# avalon_module.net
KiCad netlist of a schematic drawn in EAGLE
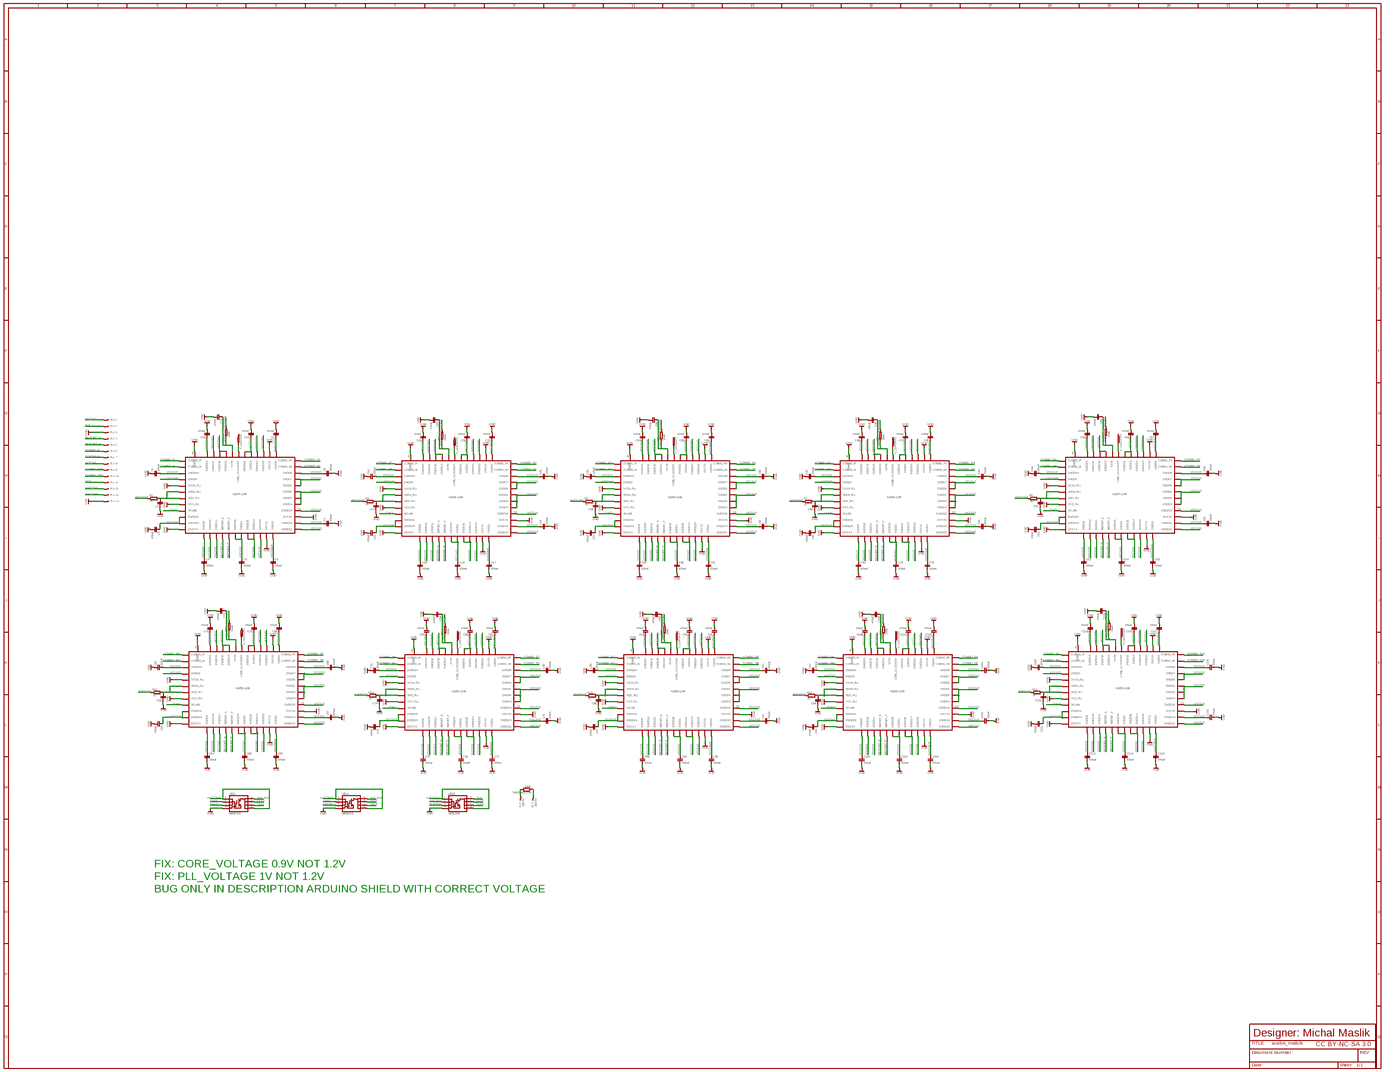
[diagram p0: schematic, sheet 1, overview]
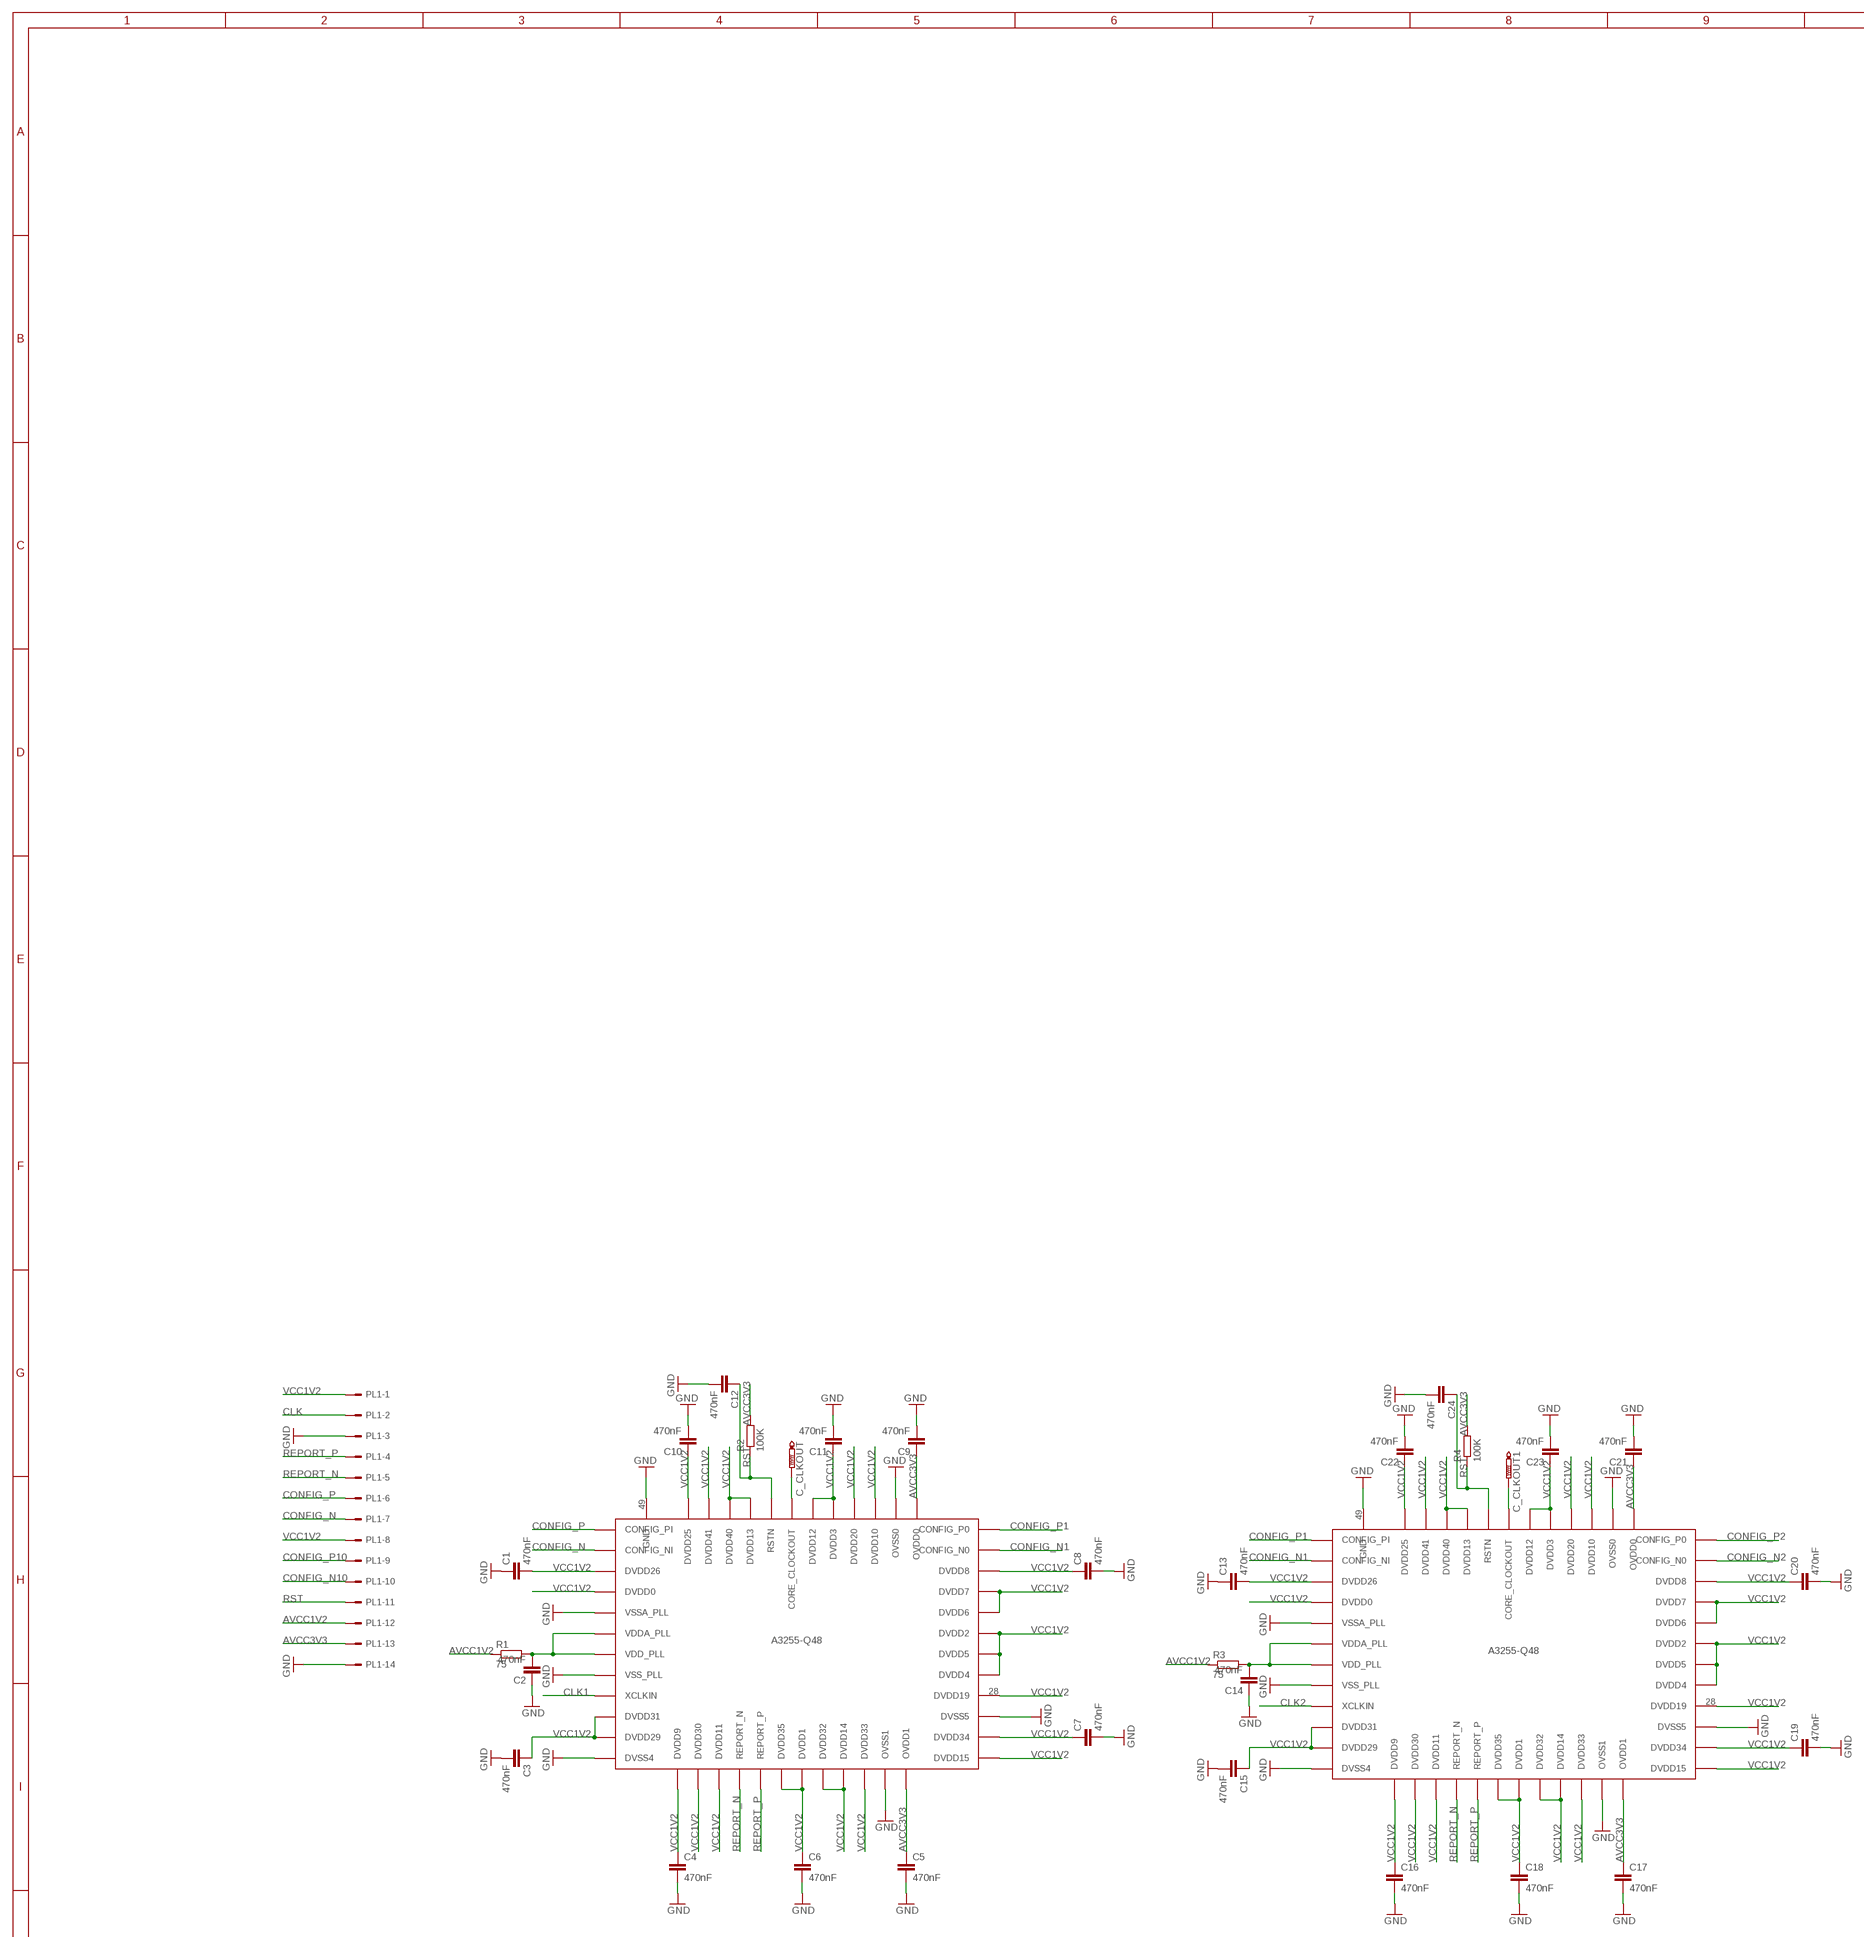
[diagram p1: schematic, sheet 1, part 1 of 6]
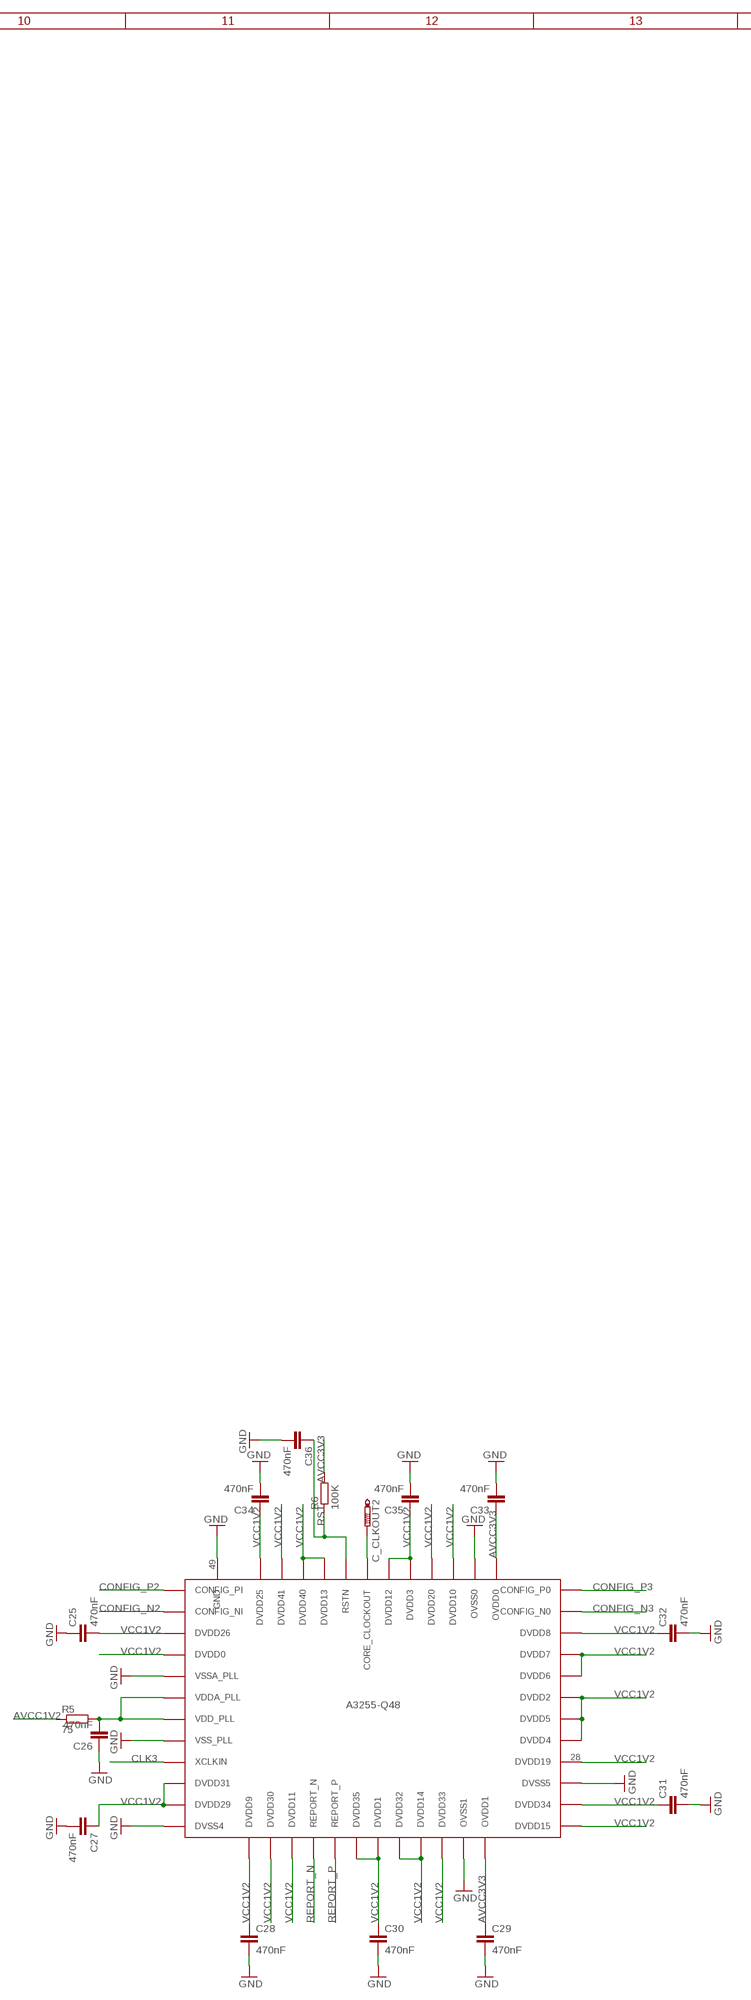
[diagram p2: schematic, sheet 1, part 2 of 6]
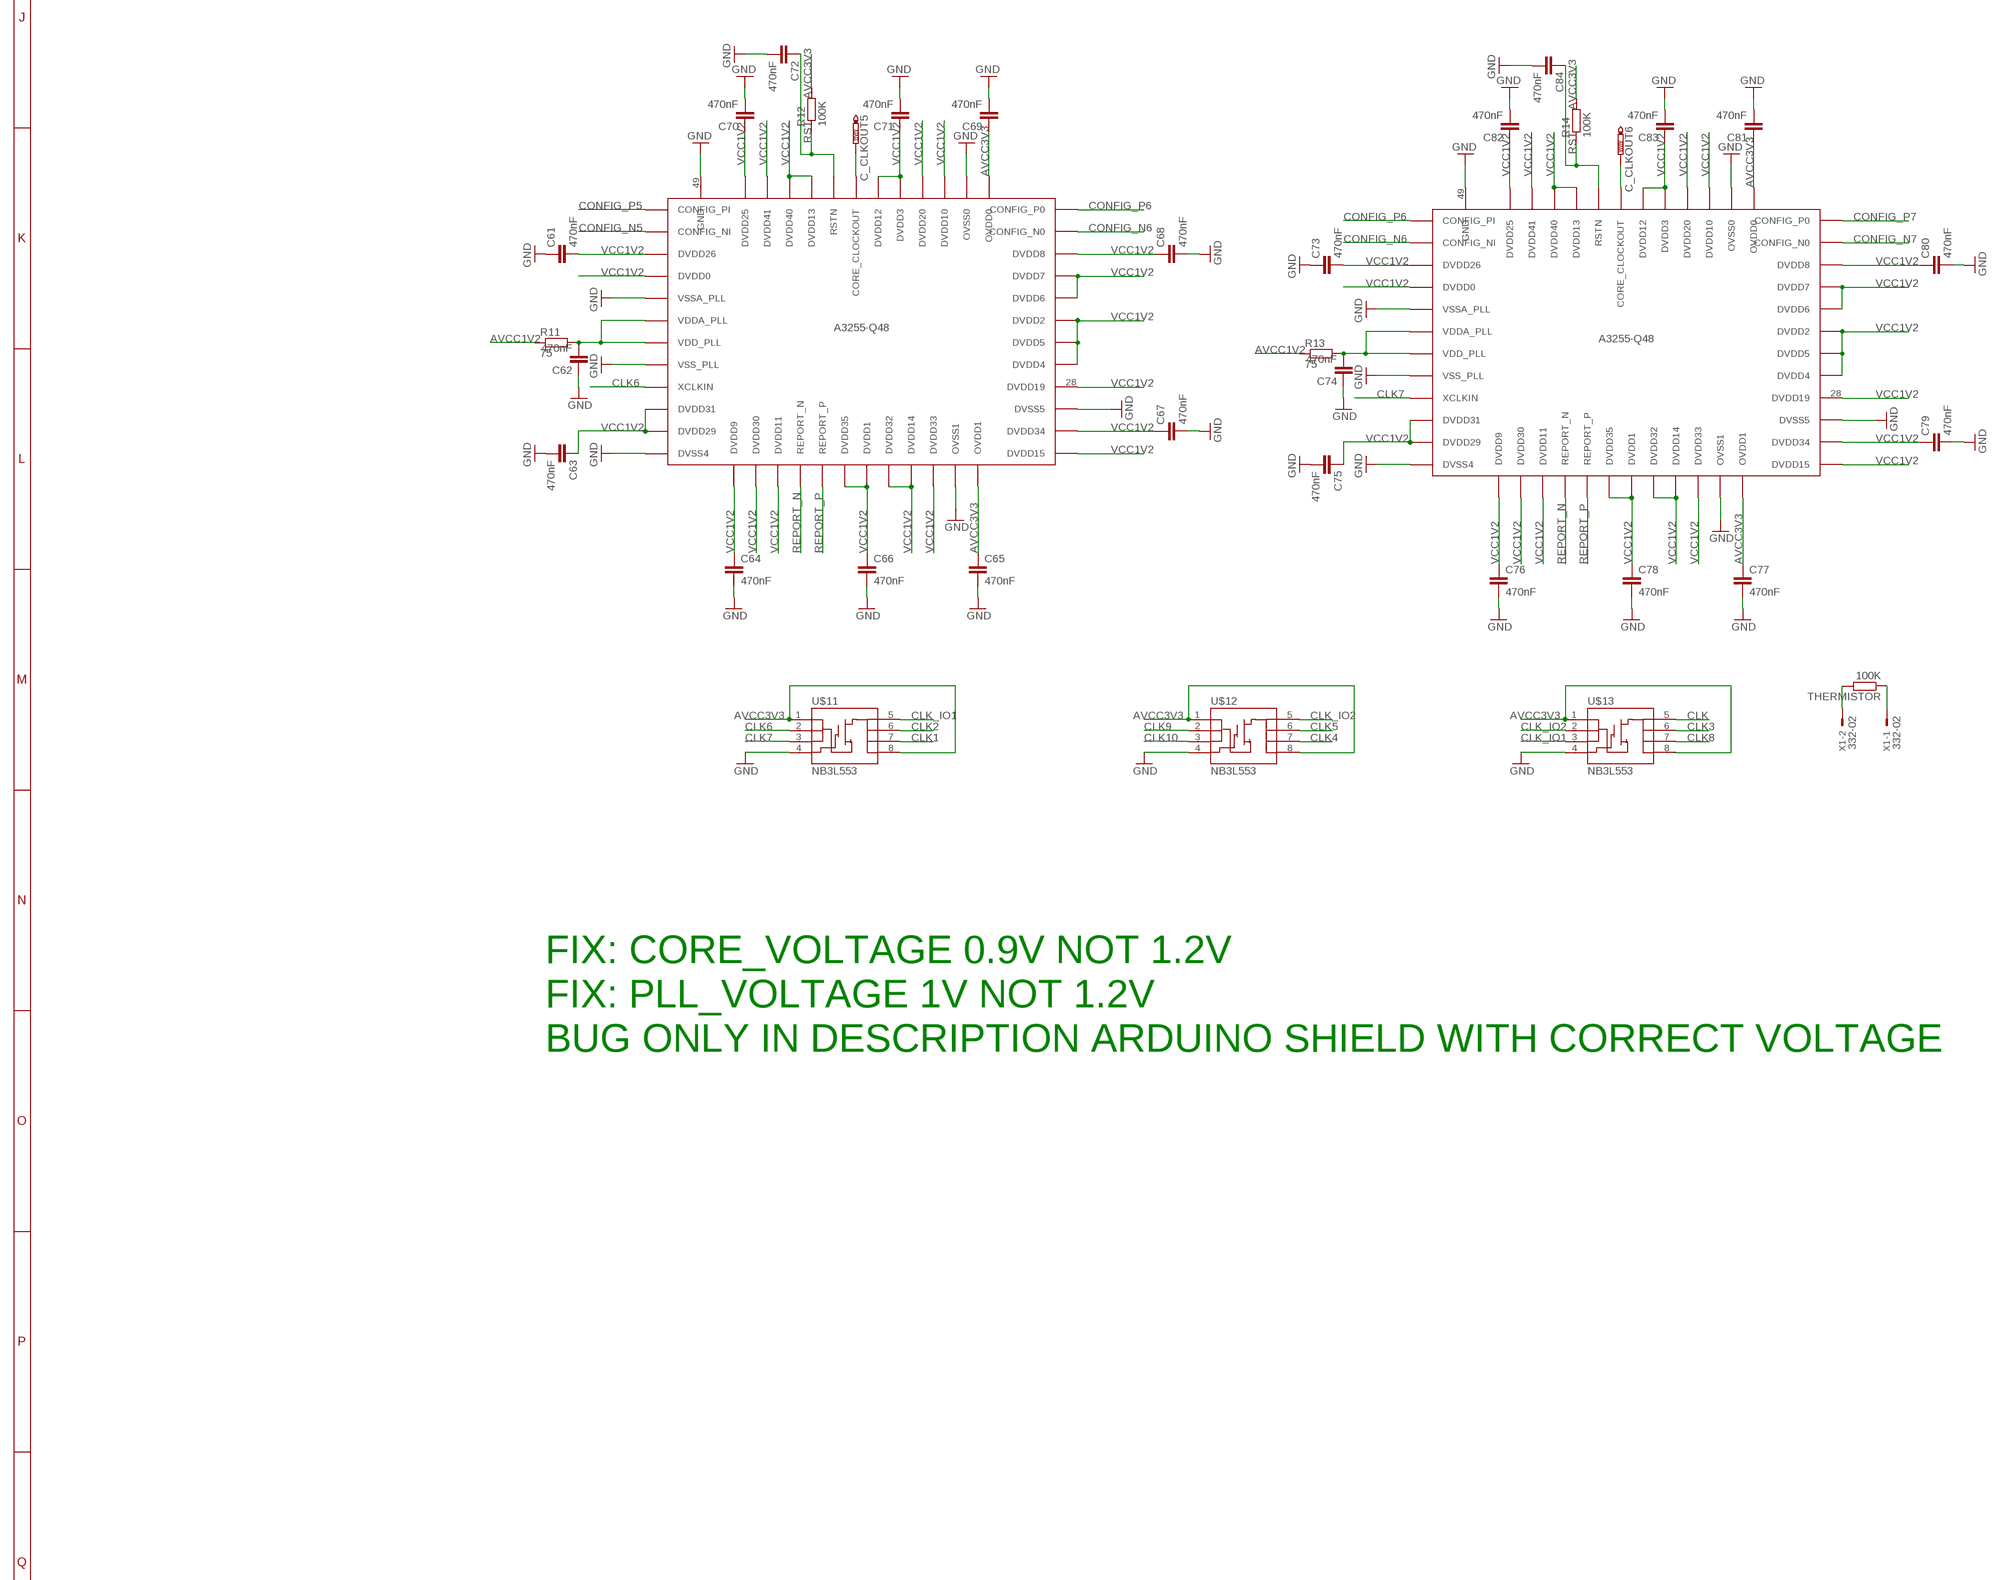
[diagram p3: schematic, sheet 1, part 3 of 6]
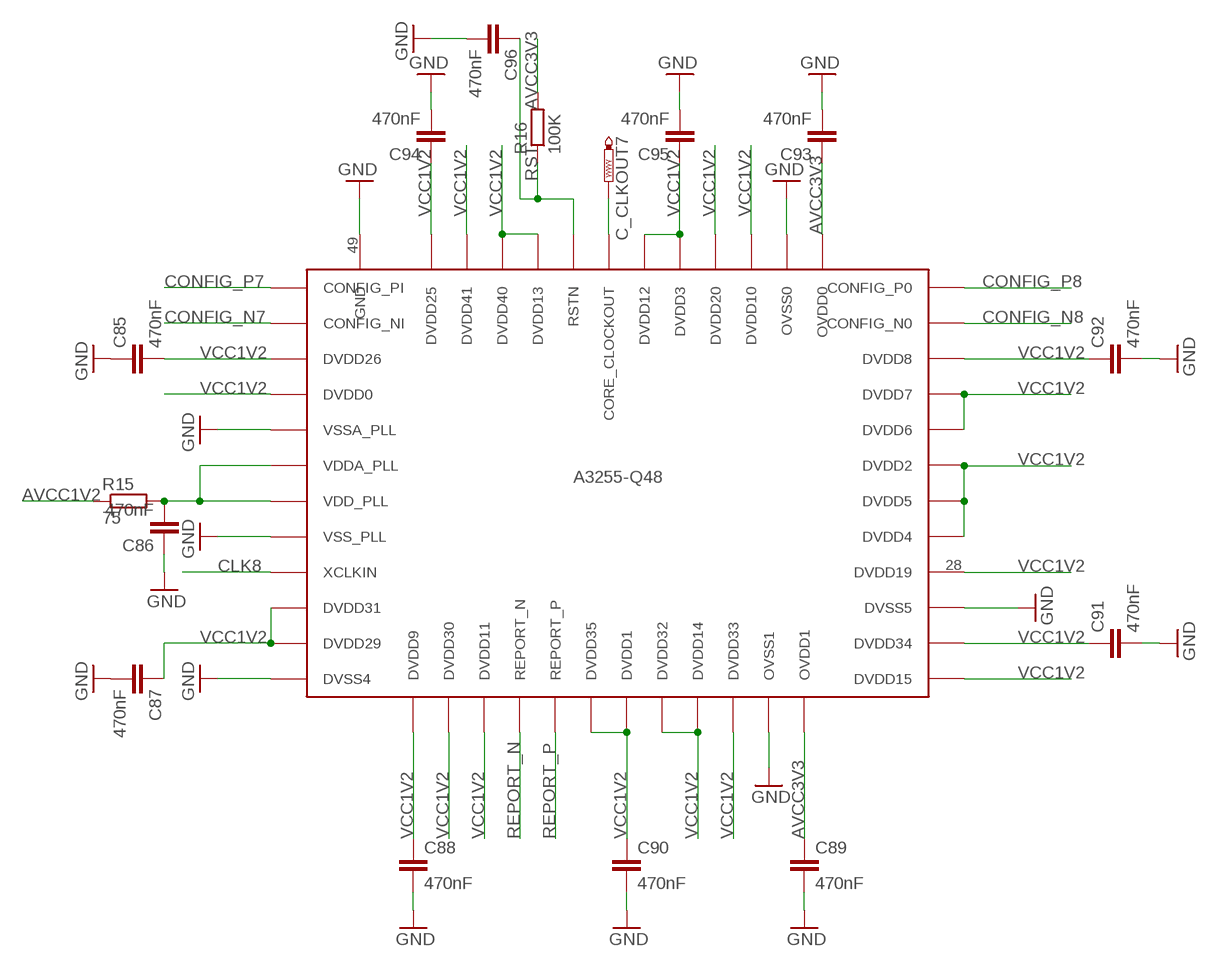
[diagram p4: schematic, sheet 1, part 4 of 6]
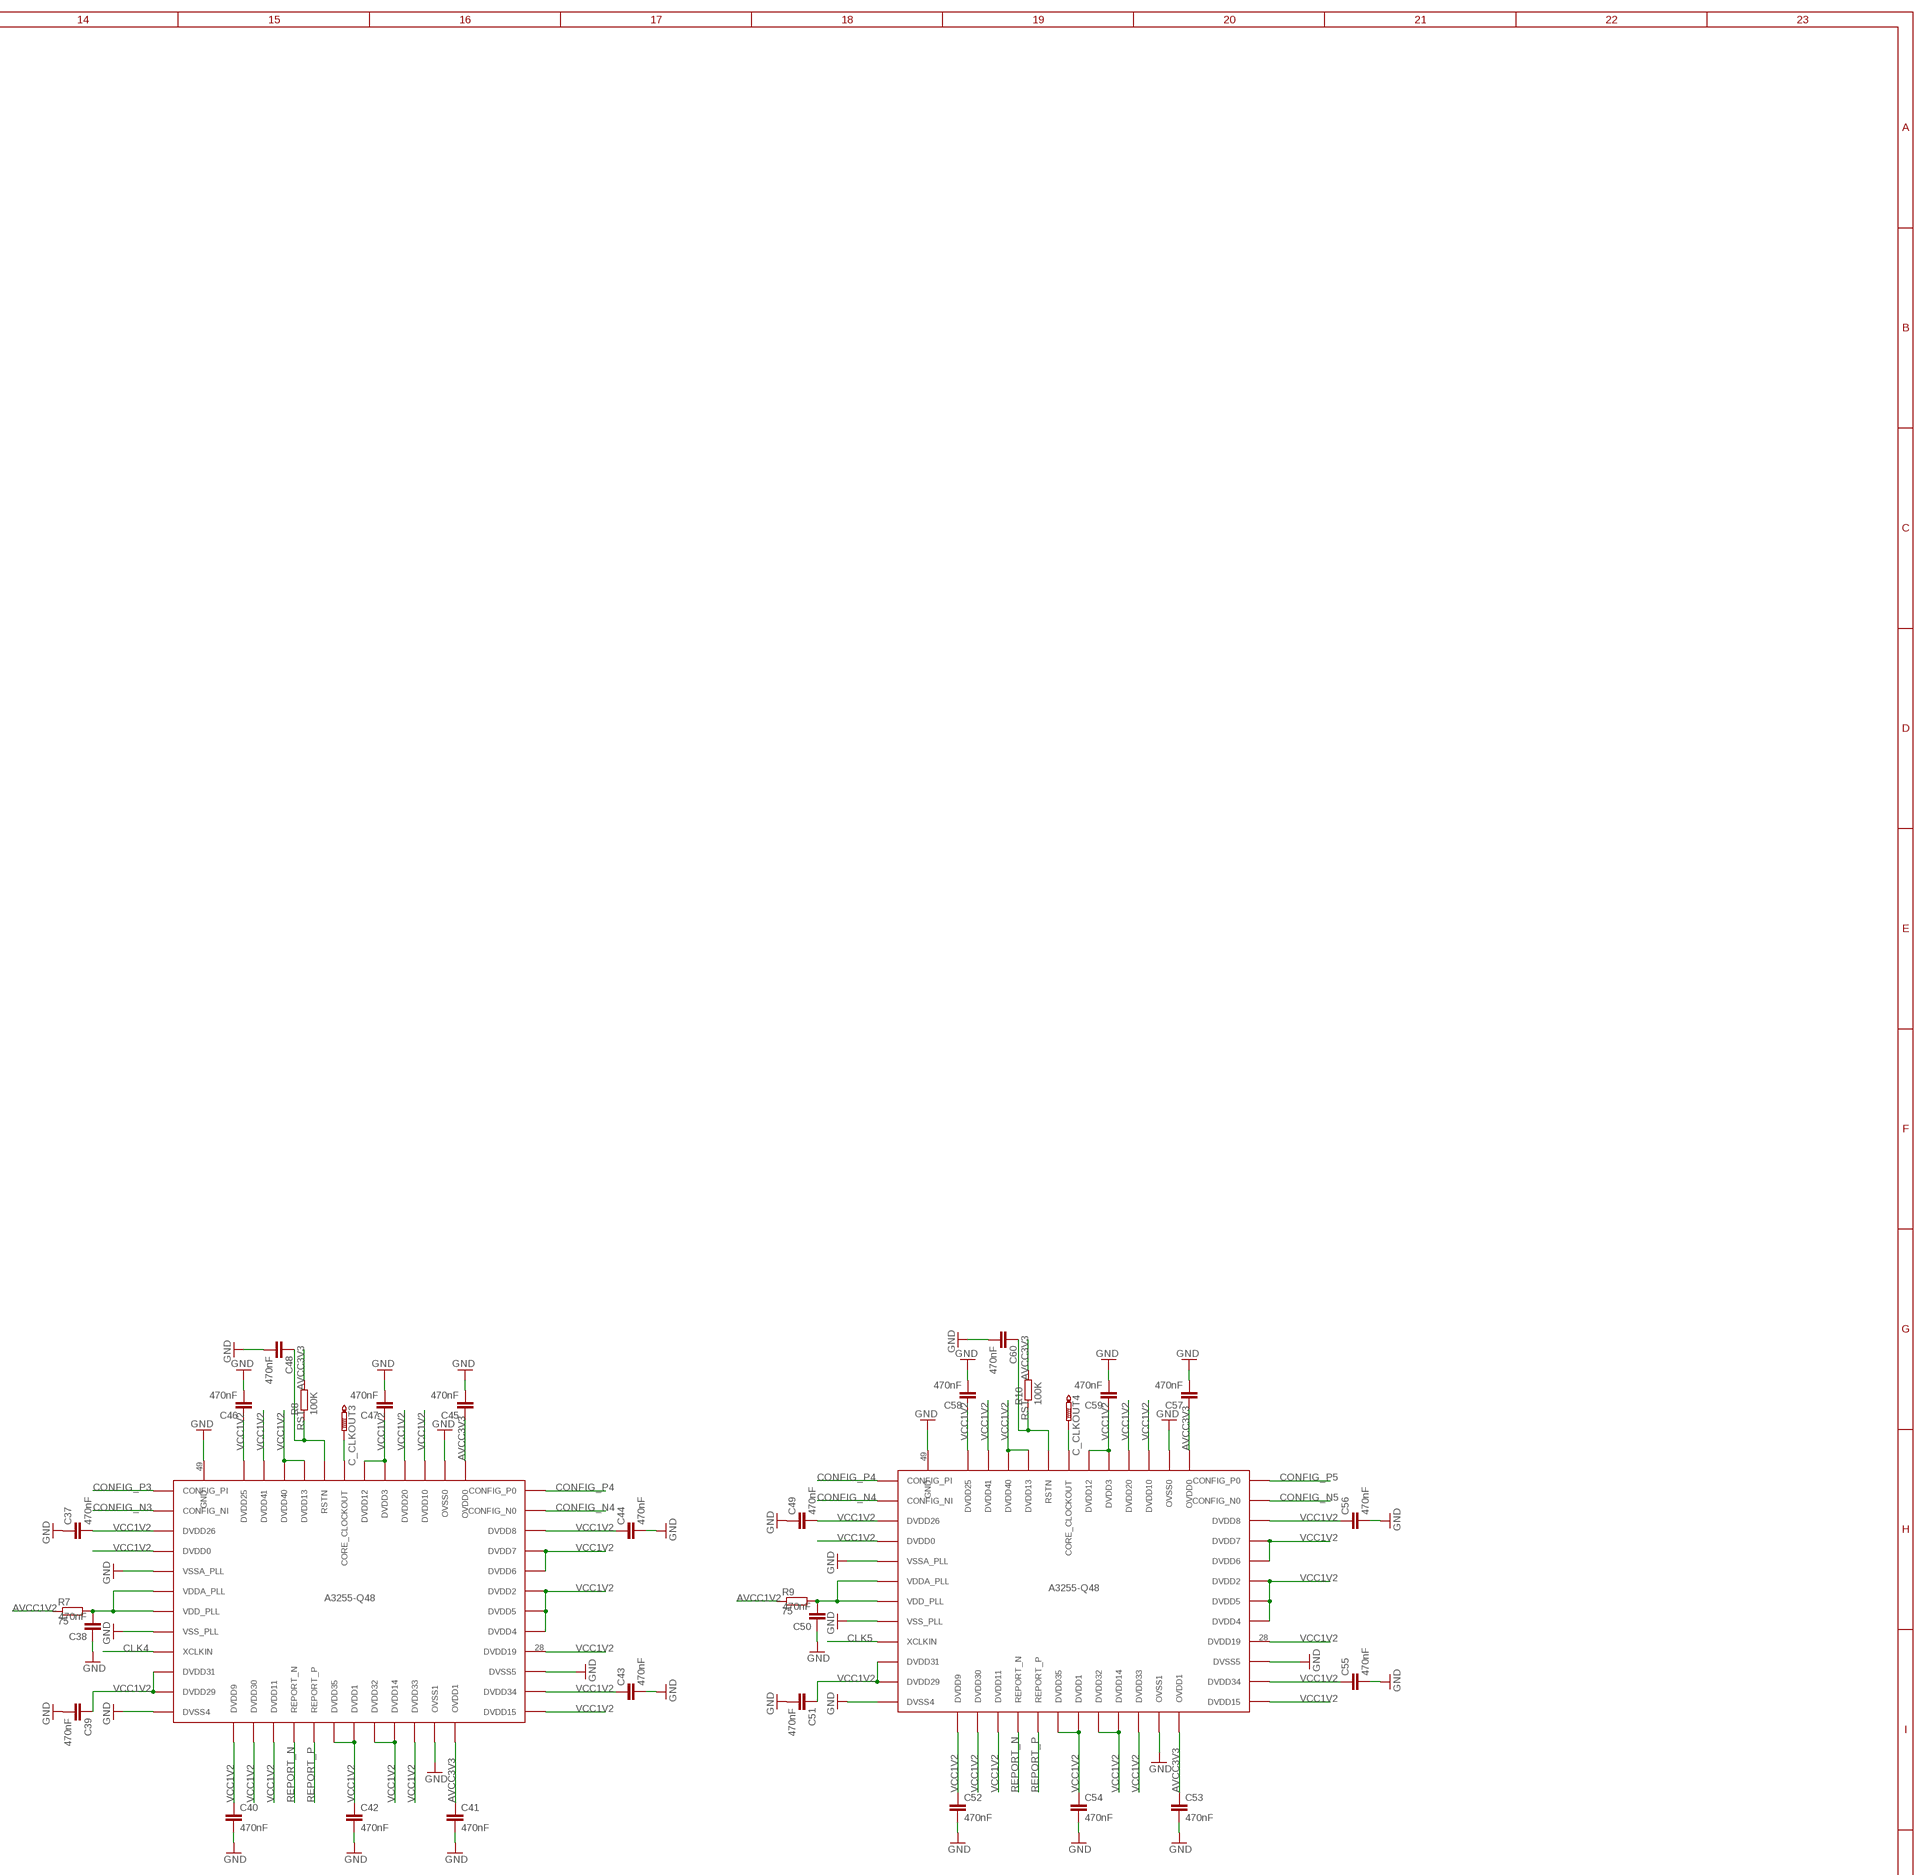
[diagram p5: schematic, sheet 1, part 5 of 6]
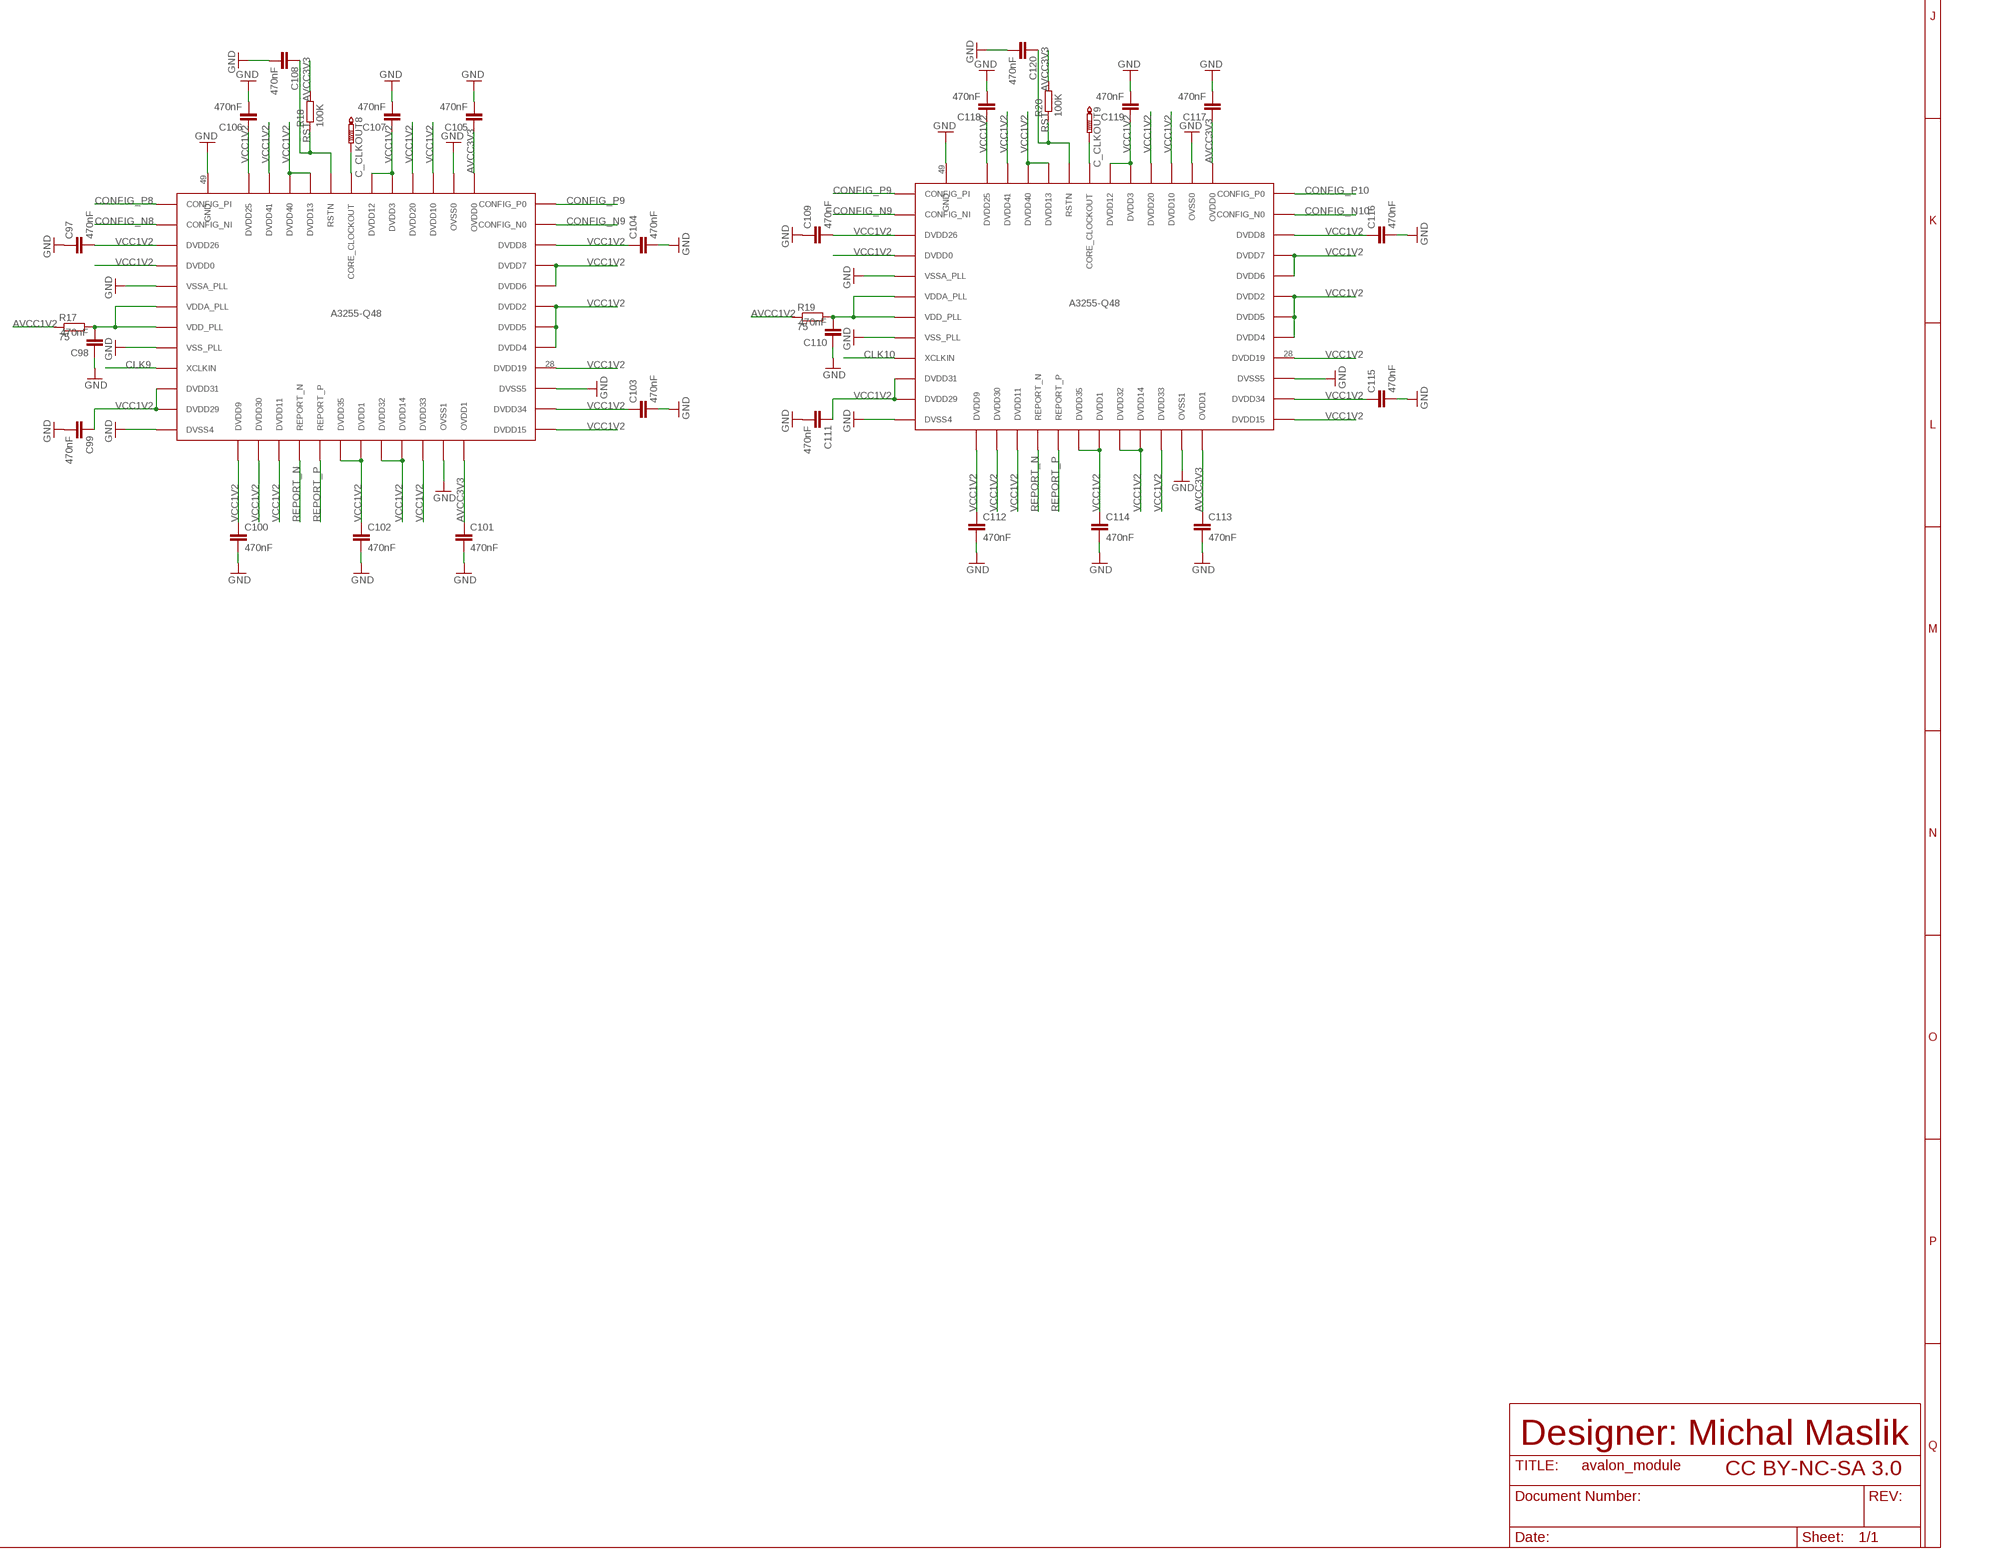
[diagram p6: schematic, sheet 1, part 6 of 6]

(export (version "E")
  (design (tool "Eeschema 10.0.6"))
  (components
    (comp (ref "C1")
      (value "470nF")
      (footprint "eagle-import:C0603K")
      (libsource (lib "eagle-import") (part "C-EUC0603K"))
    )
    (comp (ref "C2")
      (value "470nF")
      (footprint "eagle-import:C0603K")
      (libsource (lib "eagle-import") (part "C-EUC0603K"))
    )
    (comp (ref "C3")
      (value "470nF")
      (footprint "eagle-import:C0603K")
      (libsource (lib "eagle-import") (part "C-EUC0603K"))
    )
    (comp (ref "C4")
      (value "470nF")
      (footprint "eagle-import:C0603K")
      (libsource (lib "eagle-import") (part "C-EUC0603K"))
    )
    (comp (ref "C5")
      (value "470nF")
      (footprint "eagle-import:C0603K")
      (libsource (lib "eagle-import") (part "C-EUC0603K"))
    )
    (comp (ref "C6")
      (value "470nF")
      (footprint "eagle-import:C0603K")
      (libsource (lib "eagle-import") (part "C-EUC0603K"))
    )
    (comp (ref "C7")
      (value "470nF")
      (footprint "eagle-import:C0603K")
      (libsource (lib "eagle-import") (part "C-EUC0603K"))
    )
    (comp (ref "C8")
      (value "470nF")
      (footprint "eagle-import:C0603K")
      (libsource (lib "eagle-import") (part "C-EUC0603K"))
    )
    (comp (ref "C9")
      (value "470nF")
      (footprint "eagle-import:C0603K")
      (libsource (lib "eagle-import") (part "C-EUC0603K"))
    )
    (comp (ref "C10")
      (value "470nF")
      (footprint "eagle-import:C0603K")
      (libsource (lib "eagle-import") (part "C-EUC0603K"))
    )
    (comp (ref "C11")
      (value "470nF")
      (footprint "eagle-import:C0603K")
      (libsource (lib "eagle-import") (part "C-EUC0603K"))
    )
    (comp (ref "C12")
      (value "470nF")
      (footprint "eagle-import:C0603K")
      (libsource (lib "eagle-import") (part "C-EUC0603K"))
    )
    (comp (ref "C13")
      (value "470nF")
      (footprint "eagle-import:C0603K")
      (libsource (lib "eagle-import") (part "C-EUC0603K"))
    )
    (comp (ref "C14")
      (value "470nF")
      (footprint "eagle-import:C0603K")
      (libsource (lib "eagle-import") (part "C-EUC0603K"))
    )
    (comp (ref "C15")
      (value "470nF")
      (footprint "eagle-import:C0603K")
      (libsource (lib "eagle-import") (part "C-EUC0603K"))
    )
    (comp (ref "C16")
      (value "470nF")
      (footprint "eagle-import:C0603K")
      (libsource (lib "eagle-import") (part "C-EUC0603K"))
    )
    (comp (ref "C17")
      (value "470nF")
      (footprint "eagle-import:C0603K")
      (libsource (lib "eagle-import") (part "C-EUC0603K"))
    )
    (comp (ref "C18")
      (value "470nF")
      (footprint "eagle-import:C0603K")
      (libsource (lib "eagle-import") (part "C-EUC0603K"))
    )
    (comp (ref "C19")
      (value "470nF")
      (footprint "eagle-import:C0603K")
      (libsource (lib "eagle-import") (part "C-EUC0603K"))
    )
    (comp (ref "C20")
      (value "470nF")
      (footprint "eagle-import:C0603K")
      (libsource (lib "eagle-import") (part "C-EUC0603K"))
    )
    (comp (ref "C21")
      (value "470nF")
      (footprint "eagle-import:C0603K")
      (libsource (lib "eagle-import") (part "C-EUC0603K"))
    )
    (comp (ref "C22")
      (value "470nF")
      (footprint "eagle-import:C0603K")
      (libsource (lib "eagle-import") (part "C-EUC0603K"))
    )
    (comp (ref "C23")
      (value "470nF")
      (footprint "eagle-import:C0603K")
      (libsource (lib "eagle-import") (part "C-EUC0603K"))
    )
    (comp (ref "C24")
      (value "470nF")
      (footprint "eagle-import:C0603K")
      (libsource (lib "eagle-import") (part "C-EUC0603K"))
    )
    (comp (ref "C25")
      (value "470nF")
      (footprint "eagle-import:C0603K")
      (libsource (lib "eagle-import") (part "C-EUC0603K"))
    )
    (comp (ref "C26")
      (value "470nF")
      (footprint "eagle-import:C0603K")
      (libsource (lib "eagle-import") (part "C-EUC0603K"))
    )
    (comp (ref "C27")
      (value "470nF")
      (footprint "eagle-import:C0603K")
      (libsource (lib "eagle-import") (part "C-EUC0603K"))
    )
    (comp (ref "C28")
      (value "470nF")
      (footprint "eagle-import:C0603K")
      (libsource (lib "eagle-import") (part "C-EUC0603K"))
    )
    (comp (ref "C29")
      (value "470nF")
      (footprint "eagle-import:C0603K")
      (libsource (lib "eagle-import") (part "C-EUC0603K"))
    )
    (comp (ref "C30")
      (value "470nF")
      (footprint "eagle-import:C0603K")
      (libsource (lib "eagle-import") (part "C-EUC0603K"))
    )
    (comp (ref "C31")
      (value "470nF")
      (footprint "eagle-import:C0603K")
      (libsource (lib "eagle-import") (part "C-EUC0603K"))
    )
    (comp (ref "C32")
      (value "470nF")
      (footprint "eagle-import:C0603K")
      (libsource (lib "eagle-import") (part "C-EUC0603K"))
    )
    (comp (ref "C33")
      (value "470nF")
      (footprint "eagle-import:C0603K")
      (libsource (lib "eagle-import") (part "C-EUC0603K"))
    )
    (comp (ref "C34")
      (value "470nF")
      (footprint "eagle-import:C0603K")
      (libsource (lib "eagle-import") (part "C-EUC0603K"))
    )
    (comp (ref "C35")
      (value "470nF")
      (footprint "eagle-import:C0603K")
      (libsource (lib "eagle-import") (part "C-EUC0603K"))
    )
    (comp (ref "C36")
      (value "470nF")
      (footprint "eagle-import:C0603K")
      (libsource (lib "eagle-import") (part "C-EUC0603K"))
    )
    (comp (ref "C37")
      (value "470nF")
      (footprint "eagle-import:C0603K")
      (libsource (lib "eagle-import") (part "C-EUC0603K"))
    )
    (comp (ref "C38")
      (value "470nF")
      (footprint "eagle-import:C0603K")
      (libsource (lib "eagle-import") (part "C-EUC0603K"))
    )
    (comp (ref "C39")
      (value "470nF")
      (footprint "eagle-import:C0603K")
      (libsource (lib "eagle-import") (part "C-EUC0603K"))
    )
    (comp (ref "C40")
      (value "470nF")
      (footprint "eagle-import:C0603K")
      (libsource (lib "eagle-import") (part "C-EUC0603K"))
    )
    (comp (ref "C41")
      (value "470nF")
      (footprint "eagle-import:C0603K")
      (libsource (lib "eagle-import") (part "C-EUC0603K"))
    )
    (comp (ref "C42")
      (value "470nF")
      (footprint "eagle-import:C0603K")
      (libsource (lib "eagle-import") (part "C-EUC0603K"))
    )
    (comp (ref "C43")
      (value "470nF")
      (footprint "eagle-import:C0603K")
      (libsource (lib "eagle-import") (part "C-EUC0603K"))
    )
    (comp (ref "C44")
      (value "470nF")
      (footprint "eagle-import:C0603K")
      (libsource (lib "eagle-import") (part "C-EUC0603K"))
    )
    (comp (ref "C45")
      (value "470nF")
      (footprint "eagle-import:C0603K")
      (libsource (lib "eagle-import") (part "C-EUC0603K"))
    )
    (comp (ref "C46")
      (value "470nF")
      (footprint "eagle-import:C0603K")
      (libsource (lib "eagle-import") (part "C-EUC0603K"))
    )
    (comp (ref "C47")
      (value "470nF")
      (footprint "eagle-import:C0603K")
      (libsource (lib "eagle-import") (part "C-EUC0603K"))
    )
    (comp (ref "C48")
      (value "470nF")
      (footprint "eagle-import:C0603K")
      (libsource (lib "eagle-import") (part "C-EUC0603K"))
    )
    (comp (ref "C49")
      (value "470nF")
      (footprint "eagle-import:C0603K")
      (libsource (lib "eagle-import") (part "C-EUC0603K"))
    )
    (comp (ref "C50")
      (value "470nF")
      (footprint "eagle-import:C0603K")
      (libsource (lib "eagle-import") (part "C-EUC0603K"))
    )
    (comp (ref "C51")
      (value "470nF")
      (footprint "eagle-import:C0603K")
      (libsource (lib "eagle-import") (part "C-EUC0603K"))
    )
    (comp (ref "C52")
      (value "470nF")
      (footprint "eagle-import:C0603K")
      (libsource (lib "eagle-import") (part "C-EUC0603K"))
    )
    (comp (ref "C53")
      (value "470nF")
      (footprint "eagle-import:C0603K")
      (libsource (lib "eagle-import") (part "C-EUC0603K"))
    )
    (comp (ref "C54")
      (value "470nF")
      (footprint "eagle-import:C0603K")
      (libsource (lib "eagle-import") (part "C-EUC0603K"))
    )
    (comp (ref "C55")
      (value "470nF")
      (footprint "eagle-import:C0603K")
      (libsource (lib "eagle-import") (part "C-EUC0603K"))
    )
    (comp (ref "C56")
      (value "470nF")
      (footprint "eagle-import:C0603K")
      (libsource (lib "eagle-import") (part "C-EUC0603K"))
    )
    (comp (ref "C57")
      (value "470nF")
      (footprint "eagle-import:C0603K")
      (libsource (lib "eagle-import") (part "C-EUC0603K"))
    )
    (comp (ref "C58")
      (value "470nF")
      (footprint "eagle-import:C0603K")
      (libsource (lib "eagle-import") (part "C-EUC0603K"))
    )
    (comp (ref "C59")
      (value "470nF")
      (footprint "eagle-import:C0603K")
      (libsource (lib "eagle-import") (part "C-EUC0603K"))
    )
    (comp (ref "C60")
      (value "470nF")
      (footprint "eagle-import:C0603K")
      (libsource (lib "eagle-import") (part "C-EUC0603K"))
    )
    (comp (ref "C61")
      (value "470nF")
      (footprint "eagle-import:C0603K")
      (libsource (lib "eagle-import") (part "C-EUC0603K"))
    )
    (comp (ref "C62")
      (value "470nF")
      (footprint "eagle-import:C0603K")
      (libsource (lib "eagle-import") (part "C-EUC0603K"))
    )
    (comp (ref "C63")
      (value "470nF")
      (footprint "eagle-import:C0603K")
      (libsource (lib "eagle-import") (part "C-EUC0603K"))
    )
    (comp (ref "C64")
      (value "470nF")
      (footprint "eagle-import:C0603K")
      (libsource (lib "eagle-import") (part "C-EUC0603K"))
    )
    (comp (ref "C65")
      (value "470nF")
      (footprint "eagle-import:C0603K")
      (libsource (lib "eagle-import") (part "C-EUC0603K"))
    )
    (comp (ref "C66")
      (value "470nF")
      (footprint "eagle-import:C0603K")
      (libsource (lib "eagle-import") (part "C-EUC0603K"))
    )
    (comp (ref "C67")
      (value "470nF")
      (footprint "eagle-import:C0603K")
      (libsource (lib "eagle-import") (part "C-EUC0603K"))
    )
    (comp (ref "C68")
      (value "470nF")
      (footprint "eagle-import:C0603K")
      (libsource (lib "eagle-import") (part "C-EUC0603K"))
    )
    (comp (ref "C69")
      (value "470nF")
      (footprint "eagle-import:C0603K")
      (libsource (lib "eagle-import") (part "C-EUC0603K"))
    )
    (comp (ref "C70")
      (value "470nF")
      (footprint "eagle-import:C0603K")
      (libsource (lib "eagle-import") (part "C-EUC0603K"))
    )
    (comp (ref "C71")
      (value "470nF")
      (footprint "eagle-import:C0603K")
      (libsource (lib "eagle-import") (part "C-EUC0603K"))
    )
    (comp (ref "C72")
      (value "470nF")
      (footprint "eagle-import:C0603K")
      (libsource (lib "eagle-import") (part "C-EUC0603K"))
    )
    (comp (ref "C73")
      (value "470nF")
      (footprint "eagle-import:C0603K")
      (libsource (lib "eagle-import") (part "C-EUC0603K"))
    )
    (comp (ref "C74")
      (value "470nF")
      (footprint "eagle-import:C0603K")
      (libsource (lib "eagle-import") (part "C-EUC0603K"))
    )
    (comp (ref "C75")
      (value "470nF")
      (footprint "eagle-import:C0603K")
      (libsource (lib "eagle-import") (part "C-EUC0603K"))
    )
    (comp (ref "C76")
      (value "470nF")
      (footprint "eagle-import:C0603K")
      (libsource (lib "eagle-import") (part "C-EUC0603K"))
    )
    (comp (ref "C77")
      (value "470nF")
      (footprint "eagle-import:C0603K")
      (libsource (lib "eagle-import") (part "C-EUC0603K"))
    )
    (comp (ref "C78")
      (value "470nF")
      (footprint "eagle-import:C0603K")
      (libsource (lib "eagle-import") (part "C-EUC0603K"))
    )
    (comp (ref "C79")
      (value "470nF")
      (footprint "eagle-import:C0603K")
      (libsource (lib "eagle-import") (part "C-EUC0603K"))
    )
    (comp (ref "C80")
      (value "470nF")
      (footprint "eagle-import:C0603K")
      (libsource (lib "eagle-import") (part "C-EUC0603K"))
    )
    (comp (ref "C81")
      (value "470nF")
      (footprint "eagle-import:C0603K")
      (libsource (lib "eagle-import") (part "C-EUC0603K"))
    )
    (comp (ref "C82")
      (value "470nF")
      (footprint "eagle-import:C0603K")
      (libsource (lib "eagle-import") (part "C-EUC0603K"))
    )
    (comp (ref "C83")
      (value "470nF")
      (footprint "eagle-import:C0603K")
      (libsource (lib "eagle-import") (part "C-EUC0603K"))
    )
    (comp (ref "C84")
      (value "470nF")
      (footprint "eagle-import:C0603K")
      (libsource (lib "eagle-import") (part "C-EUC0603K"))
    )
    (comp (ref "C85")
      (value "470nF")
      (footprint "eagle-import:C0603K")
      (libsource (lib "eagle-import") (part "C-EUC0603K"))
    )
    (comp (ref "C86")
      (value "470nF")
      (footprint "eagle-import:C0603K")
      (libsource (lib "eagle-import") (part "C-EUC0603K"))
    )
    (comp (ref "C87")
      (value "470nF")
      (footprint "eagle-import:C0603K")
      (libsource (lib "eagle-import") (part "C-EUC0603K"))
    )
    (comp (ref "C88")
      (value "470nF")
      (footprint "eagle-import:C0603K")
      (libsource (lib "eagle-import") (part "C-EUC0603K"))
    )
    (comp (ref "C89")
      (value "470nF")
      (footprint "eagle-import:C0603K")
      (libsource (lib "eagle-import") (part "C-EUC0603K"))
    )
    (comp (ref "C90")
      (value "470nF")
      (footprint "eagle-import:C0603K")
      (libsource (lib "eagle-import") (part "C-EUC0603K"))
    )
    (comp (ref "C91")
      (value "470nF")
      (footprint "eagle-import:C0603K")
      (libsource (lib "eagle-import") (part "C-EUC0603K"))
    )
    (comp (ref "C92")
      (value "470nF")
      (footprint "eagle-import:C0603K")
      (libsource (lib "eagle-import") (part "C-EUC0603K"))
    )
    (comp (ref "C93")
      (value "470nF")
      (footprint "eagle-import:C0603K")
      (libsource (lib "eagle-import") (part "C-EUC0603K"))
    )
    (comp (ref "C94")
      (value "470nF")
      (footprint "eagle-import:C0603K")
      (libsource (lib "eagle-import") (part "C-EUC0603K"))
    )
    (comp (ref "C95")
      (value "470nF")
      (footprint "eagle-import:C0603K")
      (libsource (lib "eagle-import") (part "C-EUC0603K"))
    )
    (comp (ref "C96")
      (value "470nF")
      (footprint "eagle-import:C0603K")
      (libsource (lib "eagle-import") (part "C-EUC0603K"))
    )
    (comp (ref "C97")
      (value "470nF")
      (footprint "eagle-import:C0603K")
      (libsource (lib "eagle-import") (part "C-EUC0603K"))
    )
    (comp (ref "C98")
      (value "470nF")
      (footprint "eagle-import:C0603K")
      (libsource (lib "eagle-import") (part "C-EUC0603K"))
    )
    (comp (ref "C99")
      (value "470nF")
      (footprint "eagle-import:C0603K")
      (libsource (lib "eagle-import") (part "C-EUC0603K"))
    )
    (comp (ref "C100")
      (value "470nF")
      (footprint "eagle-import:C0603K")
      (libsource (lib "eagle-import") (part "C-EUC0603K"))
    )
    (comp (ref "C101")
      (value "470nF")
      (footprint "eagle-import:C0603K")
      (libsource (lib "eagle-import") (part "C-EUC0603K"))
    )
    (comp (ref "C102")
      (value "470nF")
      (footprint "eagle-import:C0603K")
      (libsource (lib "eagle-import") (part "C-EUC0603K"))
    )
    (comp (ref "C103")
      (value "470nF")
      (footprint "eagle-import:C0603K")
      (libsource (lib "eagle-import") (part "C-EUC0603K"))
    )
    (comp (ref "C104")
      (value "470nF")
      (footprint "eagle-import:C0603K")
      (libsource (lib "eagle-import") (part "C-EUC0603K"))
    )
    (comp (ref "C105")
      (value "470nF")
      (footprint "eagle-import:C0603K")
      (libsource (lib "eagle-import") (part "C-EUC0603K"))
    )
    (comp (ref "C106")
      (value "470nF")
      (footprint "eagle-import:C0603K")
      (libsource (lib "eagle-import") (part "C-EUC0603K"))
    )
    (comp (ref "C107")
      (value "470nF")
      (footprint "eagle-import:C0603K")
      (libsource (lib "eagle-import") (part "C-EUC0603K"))
    )
    (comp (ref "C108")
      (value "470nF")
      (footprint "eagle-import:C0603K")
      (libsource (lib "eagle-import") (part "C-EUC0603K"))
    )
    (comp (ref "C109")
      (value "470nF")
      (footprint "eagle-import:C0603K")
      (libsource (lib "eagle-import") (part "C-EUC0603K"))
    )
    (comp (ref "C110")
      (value "470nF")
      (footprint "eagle-import:C0603K")
      (libsource (lib "eagle-import") (part "C-EUC0603K"))
    )
    (comp (ref "C111")
      (value "470nF")
      (footprint "eagle-import:C0603K")
      (libsource (lib "eagle-import") (part "C-EUC0603K"))
    )
    (comp (ref "C112")
      (value "470nF")
      (footprint "eagle-import:C0603K")
      (libsource (lib "eagle-import") (part "C-EUC0603K"))
    )
    (comp (ref "C113")
      (value "470nF")
      (footprint "eagle-import:C0603K")
      (libsource (lib "eagle-import") (part "C-EUC0603K"))
    )
    (comp (ref "C114")
      (value "470nF")
      (footprint "eagle-import:C0603K")
      (libsource (lib "eagle-import") (part "C-EUC0603K"))
    )
    (comp (ref "C115")
      (value "470nF")
      (footprint "eagle-import:C0603K")
      (libsource (lib "eagle-import") (part "C-EUC0603K"))
    )
    (comp (ref "C116")
      (value "470nF")
      (footprint "eagle-import:C0603K")
      (libsource (lib "eagle-import") (part "C-EUC0603K"))
    )
    (comp (ref "C117")
      (value "470nF")
      (footprint "eagle-import:C0603K")
      (libsource (lib "eagle-import") (part "C-EUC0603K"))
    )
    (comp (ref "C118")
      (value "470nF")
      (footprint "eagle-import:C0603K")
      (libsource (lib "eagle-import") (part "C-EUC0603K"))
    )
    (comp (ref "C119")
      (value "470nF")
      (footprint "eagle-import:C0603K")
      (libsource (lib "eagle-import") (part "C-EUC0603K"))
    )
    (comp (ref "C120")
      (value "470nF")
      (footprint "eagle-import:C0603K")
      (libsource (lib "eagle-import") (part "C-EUC0603K"))
    )
    (comp (ref "C_CLKOUT")
      (value "PTR1TP07R")
      (footprint "eagle-import:TP07R")
      (libsource (lib "eagle-import") (part "PTR1TP07R"))
    )
    (comp (ref "C_CLKOUT1")
      (value "PTR1TP07R")
      (footprint "eagle-import:TP07R")
      (libsource (lib "eagle-import") (part "PTR1TP07R"))
    )
    (comp (ref "C_CLKOUT2")
      (value "PTR1TP07R")
      (footprint "eagle-import:TP07R")
      (libsource (lib "eagle-import") (part "PTR1TP07R"))
    )
    (comp (ref "C_CLKOUT3")
      (value "PTR1TP07R")
      (footprint "eagle-import:TP07R")
      (libsource (lib "eagle-import") (part "PTR1TP07R"))
    )
    (comp (ref "C_CLKOUT4")
      (value "PTR1TP07R")
      (footprint "eagle-import:TP07R")
      (libsource (lib "eagle-import") (part "PTR1TP07R"))
    )
    (comp (ref "C_CLKOUT5")
      (value "PTR1TP07R")
      (footprint "eagle-import:TP07R")
      (libsource (lib "eagle-import") (part "PTR1TP07R"))
    )
    (comp (ref "C_CLKOUT6")
      (value "PTR1TP07R")
      (footprint "eagle-import:TP07R")
      (libsource (lib "eagle-import") (part "PTR1TP07R"))
    )
    (comp (ref "C_CLKOUT7")
      (value "PTR1TP07R")
      (footprint "eagle-import:TP07R")
      (libsource (lib "eagle-import") (part "PTR1TP07R"))
    )
    (comp (ref "C_CLKOUT8")
      (value "PTR1TP07R")
      (footprint "eagle-import:TP07R")
      (libsource (lib "eagle-import") (part "PTR1TP07R"))
    )
    (comp (ref "C_CLKOUT9")
      (value "PTR1TP07R")
      (footprint "eagle-import:TP07R")
      (libsource (lib "eagle-import") (part "PTR1TP07R"))
    )
    (comp (ref "PL1")
      (value "555X-14H")
      (footprint "eagle-import:5569-14")
      (libsource (lib "eagle-import") (part "555X-14H"))
    )
    (comp (ref "R1")
      (value "75")
      (footprint "eagle-import:R0603")
      (libsource (lib "eagle-import") (part "R-EU_R0603"))
    )
    (comp (ref "R2")
      (value "100K")
      (footprint "eagle-import:R0603")
      (libsource (lib "eagle-import") (part "R-EU_R0603"))
    )
    (comp (ref "R3")
      (value "75")
      (footprint "eagle-import:R0603")
      (libsource (lib "eagle-import") (part "R-EU_R0603"))
    )
    (comp (ref "R4")
      (value "100K")
      (footprint "eagle-import:R0603")
      (libsource (lib "eagle-import") (part "R-EU_R0603"))
    )
    (comp (ref "R5")
      (value "75")
      (footprint "eagle-import:R0603")
      (libsource (lib "eagle-import") (part "R-EU_R0603"))
    )
    (comp (ref "R6")
      (value "100K")
      (footprint "eagle-import:R0603")
      (libsource (lib "eagle-import") (part "R-EU_R0603"))
    )
    (comp (ref "R7")
      (value "75")
      (footprint "eagle-import:R0603")
      (libsource (lib "eagle-import") (part "R-EU_R0603"))
    )
    (comp (ref "R8")
      (value "100K")
      (footprint "eagle-import:R0603")
      (libsource (lib "eagle-import") (part "R-EU_R0603"))
    )
    (comp (ref "R9")
      (value "75")
      (footprint "eagle-import:R0603")
      (libsource (lib "eagle-import") (part "R-EU_R0603"))
    )
    (comp (ref "R10")
      (value "100K")
      (footprint "eagle-import:R0603")
      (libsource (lib "eagle-import") (part "R-EU_R0603"))
    )
    (comp (ref "R11")
      (value "75")
      (footprint "eagle-import:R0603")
      (libsource (lib "eagle-import") (part "R-EU_R0603"))
    )
    (comp (ref "R12")
      (value "100K")
      (footprint "eagle-import:R0603")
      (libsource (lib "eagle-import") (part "R-EU_R0603"))
    )
    (comp (ref "R13")
      (value "75")
      (footprint "eagle-import:R0603")
      (libsource (lib "eagle-import") (part "R-EU_R0603"))
    )
    (comp (ref "R14")
      (value "100K")
      (footprint "eagle-import:R0603")
      (libsource (lib "eagle-import") (part "R-EU_R0603"))
    )
    (comp (ref "R15")
      (value "75")
      (footprint "eagle-import:R0603")
      (libsource (lib "eagle-import") (part "R-EU_R0603"))
    )
    (comp (ref "R16")
      (value "100K")
      (footprint "eagle-import:R0603")
      (libsource (lib "eagle-import") (part "R-EU_R0603"))
    )
    (comp (ref "R17")
      (value "75")
      (footprint "eagle-import:R0603")
      (libsource (lib "eagle-import") (part "R-EU_R0603"))
    )
    (comp (ref "R18")
      (value "100K")
      (footprint "eagle-import:R0603")
      (libsource (lib "eagle-import") (part "R-EU_R0603"))
    )
    (comp (ref "R19")
      (value "75")
      (footprint "eagle-import:R0603")
      (libsource (lib "eagle-import") (part "R-EU_R0603"))
    )
    (comp (ref "R20")
      (value "100K")
      (footprint "eagle-import:R0603")
      (libsource (lib "eagle-import") (part "R-EU_R0603"))
    )
    (comp (ref "THERMISTOR")
      (value "100K")
      (footprint "eagle-import:R0603")
      (libsource (lib "eagle-import") (part "R-EU_R0603"))
    )
    (comp (ref "U$1")
      (value "A3255Q48")
      (footprint "eagle-import:A3255Q48")
      (libsource (lib "eagle-import") (part "A3255Q48"))
    )
    (comp (ref "U$2")
      (value "A3255Q48")
      (footprint "eagle-import:A3255Q48")
      (libsource (lib "eagle-import") (part "A3255Q48"))
    )
    (comp (ref "U$3")
      (value "A3255Q48")
      (footprint "eagle-import:A3255Q48")
      (libsource (lib "eagle-import") (part "A3255Q48"))
    )
    (comp (ref "U$4")
      (value "A3255Q48")
      (footprint "eagle-import:A3255Q48")
      (libsource (lib "eagle-import") (part "A3255Q48"))
    )
    (comp (ref "U$5")
      (value "A3255Q48")
      (footprint "eagle-import:A3255Q48")
      (libsource (lib "eagle-import") (part "A3255Q48"))
    )
    (comp (ref "U$6")
      (value "A3255Q48")
      (footprint "eagle-import:A3255Q48")
      (libsource (lib "eagle-import") (part "A3255Q48"))
    )
    (comp (ref "U$7")
      (value "A3255Q48")
      (footprint "eagle-import:A3255Q48")
      (libsource (lib "eagle-import") (part "A3255Q48"))
    )
    (comp (ref "U$8")
      (value "A3255Q48")
      (footprint "eagle-import:A3255Q48")
      (libsource (lib "eagle-import") (part "A3255Q48"))
    )
    (comp (ref "U$9")
      (value "A3255Q48")
      (footprint "eagle-import:A3255Q48")
      (libsource (lib "eagle-import") (part "A3255Q48"))
    )
    (comp (ref "U$10")
      (value "A3255Q48")
      (footprint "eagle-import:A3255Q48")
      (libsource (lib "eagle-import") (part "A3255Q48"))
    )
    (comp (ref "U$11")
      (value "NB3L553")
      (footprint "eagle-import:SO08")
      (libsource (lib "eagle-import") (part "MOSFET-NCHANNEL-SOIC8"))
    )
    (comp (ref "U$12")
      (value "NB3L553")
      (footprint "eagle-import:SO08")
      (libsource (lib "eagle-import") (part "MOSFET-NCHANNEL-SOIC8"))
    )
    (comp (ref "U$13")
      (value "NB3L553")
      (footprint "eagle-import:SO08")
      (libsource (lib "eagle-import") (part "MOSFET-NCHANNEL-SOIC8"))
    )
    (comp (ref "X1")
      (value "332-02")
      (footprint "eagle-import:332-02")
      (libsource (lib "eagle-import") (part "332-02"))
    )
  )
  (nets
    (net (code "1") (name "/AVCC1V2") (class "Default")
      (node (ref "PL1") (pin "12") (pinfunction "S_12") (pintype "passive"))
      (node (ref "R1") (pin "1") (pinfunction "1_1") (pintype "passive"))
      (node (ref "R11") (pin "1") (pinfunction "1_1") (pintype "passive"))
      (node (ref "R13") (pin "1") (pinfunction "1_1") (pintype "passive"))
      (node (ref "R15") (pin "1") (pinfunction "1_1") (pintype "passive"))
      (node (ref "R17") (pin "1") (pinfunction "1_1") (pintype "passive"))
      (node (ref "R19") (pin "1") (pinfunction "1_1") (pintype "passive"))
      (node (ref "R3") (pin "1") (pinfunction "1_1") (pintype "passive"))
      (node (ref "R5") (pin "1") (pinfunction "1_1") (pintype "passive"))
      (node (ref "R7") (pin "1") (pinfunction "1_1") (pintype "passive"))
      (node (ref "R9") (pin "1") (pinfunction "1_1") (pintype "passive"))
    )
    (net (code "2") (name "/AVCC3V3") (class "Default")
      (node (ref "C101") (pin "1") (pinfunction "1_1") (pintype "passive"))
      (node (ref "C105") (pin "1") (pinfunction "1_1") (pintype "passive"))
      (node (ref "C113") (pin "1") (pinfunction "1_1") (pintype "passive"))
      (node (ref "C117") (pin "1") (pinfunction "1_1") (pintype "passive"))
      (node (ref "C17") (pin "1") (pinfunction "1_1") (pintype "passive"))
      (node (ref "C21") (pin "1") (pinfunction "1_1") (pintype "passive"))
      (node (ref "C29") (pin "1") (pinfunction "1_1") (pintype "passive"))
      (node (ref "C33") (pin "1") (pinfunction "1_1") (pintype "passive"))
      (node (ref "C41") (pin "1") (pinfunction "1_1") (pintype "passive"))
      (node (ref "C45") (pin "1") (pinfunction "1_1") (pintype "passive"))
      (node (ref "C5") (pin "1") (pinfunction "1_1") (pintype "passive"))
      (node (ref "C53") (pin "1") (pinfunction "1_1") (pintype "passive"))
      (node (ref "C57") (pin "1") (pinfunction "1_1") (pintype "passive"))
      (node (ref "C65") (pin "1") (pinfunction "1_1") (pintype "passive"))
      (node (ref "C69") (pin "1") (pinfunction "1_1") (pintype "passive"))
      (node (ref "C77") (pin "1") (pinfunction "1_1") (pintype "passive"))
      (node (ref "C81") (pin "1") (pinfunction "1_1") (pintype "passive"))
      (node (ref "C89") (pin "1") (pinfunction "1_1") (pintype "passive"))
      (node (ref "C9") (pin "1") (pinfunction "1_1") (pintype "passive"))
      (node (ref "C93") (pin "1") (pinfunction "1_1") (pintype "passive"))
      (node (ref "PL1") (pin "13") (pinfunction "S_13") (pintype "passive"))
      (node (ref "R10") (pin "2") (pinfunction "2_2") (pintype "passive"))
      (node (ref "R12") (pin "2") (pinfunction "2_2") (pintype "passive"))
      (node (ref "R14") (pin "2") (pinfunction "2_2") (pintype "passive"))
      (node (ref "R16") (pin "2") (pinfunction "2_2") (pintype "passive"))
      (node (ref "R18") (pin "2") (pinfunction "2_2") (pintype "passive"))
      (node (ref "R2") (pin "2") (pinfunction "2_2") (pintype "passive"))
      (node (ref "R20") (pin "2") (pinfunction "2_2") (pintype "passive"))
      (node (ref "R4") (pin "2") (pinfunction "2_2") (pintype "passive"))
      (node (ref "R6") (pin "2") (pinfunction "2_2") (pintype "passive"))
      (node (ref "R8") (pin "2") (pinfunction "2_2") (pintype "passive"))
      (node (ref "U$1") (pin "24") (pinfunction "OVDD1_24") (pintype "bidirectional"))
      (node (ref "U$1") (pin "37") (pinfunction "OVDD0_37") (pintype "bidirectional"))
      (node (ref "U$10") (pin "24") (pinfunction "OVDD1_24") (pintype "bidirectional"))
      (node (ref "U$10") (pin "37") (pinfunction "OVDD0_37") (pintype "bidirectional"))
      (node (ref "U$11") (pin "1") (pinfunction "S_1") (pintype "bidirectional"))
      (node (ref "U$11") (pin "8") (pinfunction "D_8") (pintype "bidirectional"))
      (node (ref "U$12") (pin "1") (pinfunction "S_1") (pintype "bidirectional"))
      (node (ref "U$12") (pin "8") (pinfunction "D_8") (pintype "bidirectional"))
      (node (ref "U$13") (pin "1") (pinfunction "S_1") (pintype "bidirectional"))
      (node (ref "U$13") (pin "8") (pinfunction "D_8") (pintype "bidirectional"))
      (node (ref "U$2") (pin "24") (pinfunction "OVDD1_24") (pintype "bidirectional"))
      (node (ref "U$2") (pin "37") (pinfunction "OVDD0_37") (pintype "bidirectional"))
      (node (ref "U$3") (pin "24") (pinfunction "OVDD1_24") (pintype "bidirectional"))
      (node (ref "U$3") (pin "37") (pinfunction "OVDD0_37") (pintype "bidirectional"))
      (node (ref "U$4") (pin "24") (pinfunction "OVDD1_24") (pintype "bidirectional"))
      (node (ref "U$4") (pin "37") (pinfunction "OVDD0_37") (pintype "bidirectional"))
      (node (ref "U$5") (pin "24") (pinfunction "OVDD1_24") (pintype "bidirectional"))
      (node (ref "U$5") (pin "37") (pinfunction "OVDD0_37") (pintype "bidirectional"))
      (node (ref "U$6") (pin "24") (pinfunction "OVDD1_24") (pintype "bidirectional"))
      (node (ref "U$6") (pin "37") (pinfunction "OVDD0_37") (pintype "bidirectional"))
      (node (ref "U$7") (pin "24") (pinfunction "OVDD1_24") (pintype "bidirectional"))
      (node (ref "U$7") (pin "37") (pinfunction "OVDD0_37") (pintype "bidirectional"))
      (node (ref "U$8") (pin "24") (pinfunction "OVDD1_24") (pintype "bidirectional"))
      (node (ref "U$8") (pin "37") (pinfunction "OVDD0_37") (pintype "bidirectional"))
      (node (ref "U$9") (pin "24") (pinfunction "OVDD1_24") (pintype "bidirectional"))
      (node (ref "U$9") (pin "37") (pinfunction "OVDD0_37") (pintype "bidirectional"))
    )
    (net (code "3") (name "/CLK") (class "Default")
      (node (ref "PL1") (pin "2") (pinfunction "S_2") (pintype "passive"))
      (node (ref "U$13") (pin "5") (pinfunction "D_5") (pintype "bidirectional"))
    )
    (net (code "4") (name "/CLK1") (class "Default")
      (node (ref "U$1") (pin "9") (pinfunction "XCLKIN_9") (pintype "bidirectional"))
      (node (ref "U$11") (pin "7") (pinfunction "D_7") (pintype "bidirectional"))
    )
    (net (code "5") (name "/CLK2") (class "Default")
      (node (ref "U$11") (pin "6") (pinfunction "D_6") (pintype "bidirectional"))
      (node (ref "U$2") (pin "9") (pinfunction "XCLKIN_9") (pintype "bidirectional"))
    )
    (net (code "6") (name "/CLK3") (class "Default")
      (node (ref "U$13") (pin "6") (pinfunction "D_6") (pintype "bidirectional"))
      (node (ref "U$3") (pin "9") (pinfunction "XCLKIN_9") (pintype "bidirectional"))
    )
    (net (code "7") (name "/CLK4") (class "Default")
      (node (ref "U$12") (pin "7") (pinfunction "D_7") (pintype "bidirectional"))
      (node (ref "U$4") (pin "9") (pinfunction "XCLKIN_9") (pintype "bidirectional"))
    )
    (net (code "8") (name "/CLK5") (class "Default")
      (node (ref "U$12") (pin "6") (pinfunction "D_6") (pintype "bidirectional"))
      (node (ref "U$5") (pin "9") (pinfunction "XCLKIN_9") (pintype "bidirectional"))
    )
    (net (code "9") (name "/CLK6") (class "Default")
      (node (ref "U$11") (pin "2") (pinfunction "S_2") (pintype "bidirectional"))
      (node (ref "U$6") (pin "9") (pinfunction "XCLKIN_9") (pintype "bidirectional"))
    )
    (net (code "10") (name "/CLK7") (class "Default")
      (node (ref "U$11") (pin "3") (pinfunction "S_3") (pintype "bidirectional"))
      (node (ref "U$7") (pin "9") (pinfunction "XCLKIN_9") (pintype "bidirectional"))
    )
    (net (code "11") (name "/CLK8") (class "Default")
      (node (ref "U$13") (pin "7") (pinfunction "D_7") (pintype "bidirectional"))
      (node (ref "U$8") (pin "9") (pinfunction "XCLKIN_9") (pintype "bidirectional"))
    )
    (net (code "12") (name "/CLK9") (class "Default")
      (node (ref "U$12") (pin "2") (pinfunction "S_2") (pintype "bidirectional"))
      (node (ref "U$9") (pin "9") (pinfunction "XCLKIN_9") (pintype "bidirectional"))
    )
    (net (code "13") (name "/CLK10") (class "Default")
      (node (ref "U$10") (pin "9") (pinfunction "XCLKIN_9") (pintype "bidirectional"))
      (node (ref "U$12") (pin "3") (pinfunction "S_3") (pintype "bidirectional"))
    )
    (net (code "14") (name "/CLK_IO1") (class "Default")
      (node (ref "U$11") (pin "5") (pinfunction "D_5") (pintype "bidirectional"))
      (node (ref "U$13") (pin "3") (pinfunction "S_3") (pintype "bidirectional"))
    )
    (net (code "15") (name "/CLK_IO2") (class "Default")
      (node (ref "U$12") (pin "5") (pinfunction "D_5") (pintype "bidirectional"))
      (node (ref "U$13") (pin "2") (pinfunction "S_2") (pintype "bidirectional"))
    )
    (net (code "16") (name "/CONFIG_N") (class "Default")
      (node (ref "PL1") (pin "7") (pinfunction "S_7") (pintype "passive"))
      (node (ref "U$1") (pin "2") (pinfunction "CONFIG_NI_2") (pintype "bidirectional"))
    )
    (net (code "17") (name "/CONFIG_N1") (class "Default")
      (node (ref "U$1") (pin "35") (pinfunction "CONFIG_N0_35") (pintype "bidirectional"))
      (node (ref "U$2") (pin "2") (pinfunction "CONFIG_NI_2") (pintype "bidirectional"))
    )
    (net (code "18") (name "/CONFIG_N2") (class "Default")
      (node (ref "U$2") (pin "35") (pinfunction "CONFIG_N0_35") (pintype "bidirectional"))
      (node (ref "U$3") (pin "2") (pinfunction "CONFIG_NI_2") (pintype "bidirectional"))
    )
    (net (code "19") (name "/CONFIG_N3") (class "Default")
      (node (ref "U$3") (pin "35") (pinfunction "CONFIG_N0_35") (pintype "bidirectional"))
      (node (ref "U$4") (pin "2") (pinfunction "CONFIG_NI_2") (pintype "bidirectional"))
    )
    (net (code "20") (name "/CONFIG_N4") (class "Default")
      (node (ref "U$4") (pin "35") (pinfunction "CONFIG_N0_35") (pintype "bidirectional"))
      (node (ref "U$5") (pin "2") (pinfunction "CONFIG_NI_2") (pintype "bidirectional"))
    )
    (net (code "21") (name "/CONFIG_N5") (class "Default")
      (node (ref "U$5") (pin "35") (pinfunction "CONFIG_N0_35") (pintype "bidirectional"))
      (node (ref "U$6") (pin "2") (pinfunction "CONFIG_NI_2") (pintype "bidirectional"))
    )
    (net (code "22") (name "/CONFIG_N6") (class "Default")
      (node (ref "U$6") (pin "35") (pinfunction "CONFIG_N0_35") (pintype "bidirectional"))
      (node (ref "U$7") (pin "2") (pinfunction "CONFIG_NI_2") (pintype "bidirectional"))
    )
    (net (code "23") (name "/CONFIG_N7") (class "Default")
      (node (ref "U$7") (pin "35") (pinfunction "CONFIG_N0_35") (pintype "bidirectional"))
      (node (ref "U$8") (pin "2") (pinfunction "CONFIG_NI_2") (pintype "bidirectional"))
    )
    (net (code "24") (name "/CONFIG_N8") (class "Default")
      (node (ref "U$8") (pin "35") (pinfunction "CONFIG_N0_35") (pintype "bidirectional"))
      (node (ref "U$9") (pin "2") (pinfunction "CONFIG_NI_2") (pintype "bidirectional"))
    )
    (net (code "25") (name "/CONFIG_N9") (class "Default")
      (node (ref "U$10") (pin "2") (pinfunction "CONFIG_NI_2") (pintype "bidirectional"))
      (node (ref "U$9") (pin "35") (pinfunction "CONFIG_N0_35") (pintype "bidirectional"))
    )
    (net (code "26") (name "/CONFIG_N10") (class "Default")
      (node (ref "PL1") (pin "10") (pinfunction "S_10") (pintype "passive"))
      (node (ref "U$10") (pin "35") (pinfunction "CONFIG_N0_35") (pintype "bidirectional"))
    )
    (net (code "27") (name "/CONFIG_P") (class "Default")
      (node (ref "PL1") (pin "6") (pinfunction "S_6") (pintype "passive"))
      (node (ref "U$1") (pin "1") (pinfunction "CONFIG_PI_1") (pintype "bidirectional"))
    )
    (net (code "28") (name "/CONFIG_P1") (class "Default")
      (node (ref "U$1") (pin "36") (pinfunction "CONFIG_P0_36") (pintype "bidirectional"))
      (node (ref "U$2") (pin "1") (pinfunction "CONFIG_PI_1") (pintype "bidirectional"))
    )
    (net (code "29") (name "/CONFIG_P2") (class "Default")
      (node (ref "U$2") (pin "36") (pinfunction "CONFIG_P0_36") (pintype "bidirectional"))
      (node (ref "U$3") (pin "1") (pinfunction "CONFIG_PI_1") (pintype "bidirectional"))
    )
    (net (code "30") (name "/CONFIG_P3") (class "Default")
      (node (ref "U$3") (pin "36") (pinfunction "CONFIG_P0_36") (pintype "bidirectional"))
      (node (ref "U$4") (pin "1") (pinfunction "CONFIG_PI_1") (pintype "bidirectional"))
    )
    (net (code "31") (name "/CONFIG_P4") (class "Default")
      (node (ref "U$4") (pin "36") (pinfunction "CONFIG_P0_36") (pintype "bidirectional"))
      (node (ref "U$5") (pin "1") (pinfunction "CONFIG_PI_1") (pintype "bidirectional"))
    )
    (net (code "32") (name "/CONFIG_P5") (class "Default")
      (node (ref "U$5") (pin "36") (pinfunction "CONFIG_P0_36") (pintype "bidirectional"))
      (node (ref "U$6") (pin "1") (pinfunction "CONFIG_PI_1") (pintype "bidirectional"))
    )
    (net (code "33") (name "/CONFIG_P6") (class "Default")
      (node (ref "U$6") (pin "36") (pinfunction "CONFIG_P0_36") (pintype "bidirectional"))
      (node (ref "U$7") (pin "1") (pinfunction "CONFIG_PI_1") (pintype "bidirectional"))
    )
    (net (code "34") (name "/CONFIG_P7") (class "Default")
      (node (ref "U$7") (pin "36") (pinfunction "CONFIG_P0_36") (pintype "bidirectional"))
      (node (ref "U$8") (pin "1") (pinfunction "CONFIG_PI_1") (pintype "bidirectional"))
    )
    (net (code "35") (name "/CONFIG_P8") (class "Default")
      (node (ref "U$8") (pin "36") (pinfunction "CONFIG_P0_36") (pintype "bidirectional"))
      (node (ref "U$9") (pin "1") (pinfunction "CONFIG_PI_1") (pintype "bidirectional"))
    )
    (net (code "36") (name "/CONFIG_P9") (class "Default")
      (node (ref "U$10") (pin "1") (pinfunction "CONFIG_PI_1") (pintype "bidirectional"))
      (node (ref "U$9") (pin "36") (pinfunction "CONFIG_P0_36") (pintype "bidirectional"))
    )
    (net (code "37") (name "/CONFIG_P10") (class "Default")
      (node (ref "PL1") (pin "9") (pinfunction "S_9") (pintype "passive"))
      (node (ref "U$10") (pin "36") (pinfunction "CONFIG_P0_36") (pintype "bidirectional"))
    )
    (net (code "38") (name "/REPORT_N") (class "Default")
      (node (ref "PL1") (pin "5") (pinfunction "S_5") (pintype "passive"))
      (node (ref "U$1") (pin "16") (pinfunction "REPORT_N_16") (pintype "bidirectional"))
      (node (ref "U$10") (pin "16") (pinfunction "REPORT_N_16") (pintype "bidirectional"))
      (node (ref "U$2") (pin "16") (pinfunction "REPORT_N_16") (pintype "bidirectional"))
      (node (ref "U$3") (pin "16") (pinfunction "REPORT_N_16") (pintype "bidirectional"))
      (node (ref "U$4") (pin "16") (pinfunction "REPORT_N_16") (pintype "bidirectional"))
      (node (ref "U$5") (pin "16") (pinfunction "REPORT_N_16") (pintype "bidirectional"))
      (node (ref "U$6") (pin "16") (pinfunction "REPORT_N_16") (pintype "bidirectional"))
      (node (ref "U$7") (pin "16") (pinfunction "REPORT_N_16") (pintype "bidirectional"))
      (node (ref "U$8") (pin "16") (pinfunction "REPORT_N_16") (pintype "bidirectional"))
      (node (ref "U$9") (pin "16") (pinfunction "REPORT_N_16") (pintype "bidirectional"))
    )
    (net (code "39") (name "/REPORT_P") (class "Default")
      (node (ref "PL1") (pin "4") (pinfunction "S_4") (pintype "passive"))
      (node (ref "U$1") (pin "17") (pinfunction "REPORT_P_17") (pintype "bidirectional"))
      (node (ref "U$10") (pin "17") (pinfunction "REPORT_P_17") (pintype "bidirectional"))
      (node (ref "U$2") (pin "17") (pinfunction "REPORT_P_17") (pintype "bidirectional"))
      (node (ref "U$3") (pin "17") (pinfunction "REPORT_P_17") (pintype "bidirectional"))
      (node (ref "U$4") (pin "17") (pinfunction "REPORT_P_17") (pintype "bidirectional"))
      (node (ref "U$5") (pin "17") (pinfunction "REPORT_P_17") (pintype "bidirectional"))
      (node (ref "U$6") (pin "17") (pinfunction "REPORT_P_17") (pintype "bidirectional"))
      (node (ref "U$7") (pin "17") (pinfunction "REPORT_P_17") (pintype "bidirectional"))
      (node (ref "U$8") (pin "17") (pinfunction "REPORT_P_17") (pintype "bidirectional"))
      (node (ref "U$9") (pin "17") (pinfunction "REPORT_P_17") (pintype "bidirectional"))
    )
    (net (code "40") (name "/RST") (class "Default")
      (node (ref "C108") (pin "1") (pinfunction "1_1") (pintype "passive"))
      (node (ref "C12") (pin "1") (pinfunction "1_1") (pintype "passive"))
      (node (ref "C120") (pin "1") (pinfunction "1_1") (pintype "passive"))
      (node (ref "C24") (pin "1") (pinfunction "1_1") (pintype "passive"))
      (node (ref "C36") (pin "1") (pinfunction "1_1") (pintype "passive"))
      (node (ref "C48") (pin "1") (pinfunction "1_1") (pintype "passive"))
      (node (ref "C60") (pin "1") (pinfunction "1_1") (pintype "passive"))
      (node (ref "C72") (pin "1") (pinfunction "1_1") (pintype "passive"))
      (node (ref "C84") (pin "1") (pinfunction "1_1") (pintype "passive"))
      (node (ref "C96") (pin "1") (pinfunction "1_1") (pintype "passive"))
      (node (ref "PL1") (pin "11") (pinfunction "S_11") (pintype "passive"))
      (node (ref "R10") (pin "1") (pinfunction "1_1") (pintype "passive"))
      (node (ref "R12") (pin "1") (pinfunction "1_1") (pintype "passive"))
      (node (ref "R14") (pin "1") (pinfunction "1_1") (pintype "passive"))
      (node (ref "R16") (pin "1") (pinfunction "1_1") (pintype "passive"))
      (node (ref "R18") (pin "1") (pinfunction "1_1") (pintype "passive"))
      (node (ref "R2") (pin "1") (pinfunction "1_1") (pintype "passive"))
      (node (ref "R20") (pin "1") (pinfunction "1_1") (pintype "passive"))
      (node (ref "R4") (pin "1") (pinfunction "1_1") (pintype "passive"))
      (node (ref "R6") (pin "1") (pinfunction "1_1") (pintype "passive"))
      (node (ref "R8") (pin "1") (pinfunction "1_1") (pintype "passive"))
      (node (ref "U$1") (pin "44") (pinfunction "RSTN_44") (pintype "bidirectional"))
      (node (ref "U$10") (pin "44") (pinfunction "RSTN_44") (pintype "bidirectional"))
      (node (ref "U$2") (pin "44") (pinfunction "RSTN_44") (pintype "bidirectional"))
      (node (ref "U$3") (pin "44") (pinfunction "RSTN_44") (pintype "bidirectional"))
      (node (ref "U$4") (pin "44") (pinfunction "RSTN_44") (pintype "bidirectional"))
      (node (ref "U$5") (pin "44") (pinfunction "RSTN_44") (pintype "bidirectional"))
      (node (ref "U$6") (pin "44") (pinfunction "RSTN_44") (pintype "bidirectional"))
      (node (ref "U$7") (pin "44") (pinfunction "RSTN_44") (pintype "bidirectional"))
      (node (ref "U$8") (pin "44") (pinfunction "RSTN_44") (pintype "bidirectional"))
      (node (ref "U$9") (pin "44") (pinfunction "RSTN_44") (pintype "bidirectional"))
    )
    (net (code "41") (name "/VCC1V2") (class "Default")
      (node (ref "C1") (pin "2") (pinfunction "2_2") (pintype "passive"))
      (node (ref "C10") (pin "1") (pinfunction "1_1") (pintype "passive"))
      (node (ref "C100") (pin "1") (pinfunction "1_1") (pintype "passive"))
      (node (ref "C102") (pin "1") (pinfunction "1_1") (pintype "passive"))
      (node (ref "C103") (pin "1") (pinfunction "1_1") (pintype "passive"))
      (node (ref "C104") (pin "1") (pinfunction "1_1") (pintype "passive"))
      (node (ref "C106") (pin "1") (pinfunction "1_1") (pintype "passive"))
      (node (ref "C107") (pin "1") (pinfunction "1_1") (pintype "passive"))
      (node (ref "C109") (pin "2") (pinfunction "2_2") (pintype "passive"))
      (node (ref "C11") (pin "1") (pinfunction "1_1") (pintype "passive"))
      (node (ref "C111") (pin "1") (pinfunction "1_1") (pintype "passive"))
      (node (ref "C112") (pin "1") (pinfunction "1_1") (pintype "passive"))
      (node (ref "C114") (pin "1") (pinfunction "1_1") (pintype "passive"))
      (node (ref "C115") (pin "1") (pinfunction "1_1") (pintype "passive"))
      (node (ref "C116") (pin "1") (pinfunction "1_1") (pintype "passive"))
      (node (ref "C118") (pin "1") (pinfunction "1_1") (pintype "passive"))
      (node (ref "C119") (pin "1") (pinfunction "1_1") (pintype "passive"))
      (node (ref "C13") (pin "2") (pinfunction "2_2") (pintype "passive"))
      (node (ref "C15") (pin "1") (pinfunction "1_1") (pintype "passive"))
      (node (ref "C16") (pin "1") (pinfunction "1_1") (pintype "passive"))
      (node (ref "C18") (pin "1") (pinfunction "1_1") (pintype "passive"))
      (node (ref "C19") (pin "1") (pinfunction "1_1") (pintype "passive"))
      (node (ref "C20") (pin "1") (pinfunction "1_1") (pintype "passive"))
      (node (ref "C22") (pin "1") (pinfunction "1_1") (pintype "passive"))
      (node (ref "C23") (pin "1") (pinfunction "1_1") (pintype "passive"))
      (node (ref "C25") (pin "2") (pinfunction "2_2") (pintype "passive"))
      (node (ref "C27") (pin "1") (pinfunction "1_1") (pintype "passive"))
      (node (ref "C28") (pin "1") (pinfunction "1_1") (pintype "passive"))
      (node (ref "C3") (pin "1") (pinfunction "1_1") (pintype "passive"))
      (node (ref "C30") (pin "1") (pinfunction "1_1") (pintype "passive"))
      (node (ref "C31") (pin "1") (pinfunction "1_1") (pintype "passive"))
      (node (ref "C32") (pin "1") (pinfunction "1_1") (pintype "passive"))
      (node (ref "C34") (pin "1") (pinfunction "1_1") (pintype "passive"))
      (node (ref "C35") (pin "1") (pinfunction "1_1") (pintype "passive"))
      (node (ref "C37") (pin "2") (pinfunction "2_2") (pintype "passive"))
      (node (ref "C39") (pin "1") (pinfunction "1_1") (pintype "passive"))
      (node (ref "C4") (pin "1") (pinfunction "1_1") (pintype "passive"))
      (node (ref "C40") (pin "1") (pinfunction "1_1") (pintype "passive"))
      (node (ref "C42") (pin "1") (pinfunction "1_1") (pintype "passive"))
      (node (ref "C43") (pin "1") (pinfunction "1_1") (pintype "passive"))
      (node (ref "C44") (pin "1") (pinfunction "1_1") (pintype "passive"))
      (node (ref "C46") (pin "1") (pinfunction "1_1") (pintype "passive"))
      (node (ref "C47") (pin "1") (pinfunction "1_1") (pintype "passive"))
      (node (ref "C49") (pin "2") (pinfunction "2_2") (pintype "passive"))
      (node (ref "C51") (pin "1") (pinfunction "1_1") (pintype "passive"))
      (node (ref "C52") (pin "1") (pinfunction "1_1") (pintype "passive"))
      (node (ref "C54") (pin "1") (pinfunction "1_1") (pintype "passive"))
      (node (ref "C55") (pin "1") (pinfunction "1_1") (pintype "passive"))
      (node (ref "C56") (pin "1") (pinfunction "1_1") (pintype "passive"))
      (node (ref "C58") (pin "1") (pinfunction "1_1") (pintype "passive"))
      (node (ref "C59") (pin "1") (pinfunction "1_1") (pintype "passive"))
      (node (ref "C6") (pin "1") (pinfunction "1_1") (pintype "passive"))
      (node (ref "C61") (pin "2") (pinfunction "2_2") (pintype "passive"))
      (node (ref "C63") (pin "1") (pinfunction "1_1") (pintype "passive"))
      (node (ref "C64") (pin "1") (pinfunction "1_1") (pintype "passive"))
      (node (ref "C66") (pin "1") (pinfunction "1_1") (pintype "passive"))
      (node (ref "C67") (pin "1") (pinfunction "1_1") (pintype "passive"))
      (node (ref "C68") (pin "1") (pinfunction "1_1") (pintype "passive"))
      (node (ref "C7") (pin "1") (pinfunction "1_1") (pintype "passive"))
      (node (ref "C70") (pin "1") (pinfunction "1_1") (pintype "passive"))
      (node (ref "C71") (pin "1") (pinfunction "1_1") (pintype "passive"))
      (node (ref "C73") (pin "2") (pinfunction "2_2") (pintype "passive"))
      (node (ref "C75") (pin "1") (pinfunction "1_1") (pintype "passive"))
      (node (ref "C76") (pin "1") (pinfunction "1_1") (pintype "passive"))
      (node (ref "C78") (pin "1") (pinfunction "1_1") (pintype "passive"))
      (node (ref "C79") (pin "1") (pinfunction "1_1") (pintype "passive"))
      (node (ref "C8") (pin "1") (pinfunction "1_1") (pintype "passive"))
      (node (ref "C80") (pin "1") (pinfunction "1_1") (pintype "passive"))
      (node (ref "C82") (pin "1") (pinfunction "1_1") (pintype "passive"))
      (node (ref "C83") (pin "1") (pinfunction "1_1") (pintype "passive"))
      (node (ref "C85") (pin "2") (pinfunction "2_2") (pintype "passive"))
      (node (ref "C87") (pin "1") (pinfunction "1_1") (pintype "passive"))
      (node (ref "C88") (pin "1") (pinfunction "1_1") (pintype "passive"))
      (node (ref "C90") (pin "1") (pinfunction "1_1") (pintype "passive"))
      (node (ref "C91") (pin "1") (pinfunction "1_1") (pintype "passive"))
      (node (ref "C92") (pin "1") (pinfunction "1_1") (pintype "passive"))
      (node (ref "C94") (pin "1") (pinfunction "1_1") (pintype "passive"))
      (node (ref "C95") (pin "1") (pinfunction "1_1") (pintype "passive"))
      (node (ref "C97") (pin "2") (pinfunction "2_2") (pintype "passive"))
      (node (ref "C99") (pin "1") (pinfunction "1_1") (pintype "passive"))
      (node (ref "PL1") (pin "1") (pinfunction "S_1") (pintype "passive"))
      (node (ref "PL1") (pin "8") (pinfunction "S_8") (pintype "passive"))
      (node (ref "U$1") (pin "10") (pinfunction "DVDD31_10") (pintype "bidirectional"))
      (node (ref "U$1") (pin "11") (pinfunction "DVDD29_11") (pintype "bidirectional"))
      (node (ref "U$1") (pin "13") (pinfunction "DVDD9_13") (pintype "bidirectional"))
      (node (ref "U$1") (pin "14") (pinfunction "DVDD30_14") (pintype "bidirectional"))
      (node (ref "U$1") (pin "15") (pinfunction "DVDD11_15") (pintype "bidirectional"))
      (node (ref "U$1") (pin "18") (pinfunction "DVDD35_18") (pintype "bidirectional"))
      (node (ref "U$1") (pin "19") (pinfunction "DVDD1_19") (pintype "bidirectional"))
      (node (ref "U$1") (pin "20") (pinfunction "DVDD32_20") (pintype "bidirectional"))
      (node (ref "U$1") (pin "21") (pinfunction "DVDD14_21") (pintype "bidirectional"))
      (node (ref "U$1") (pin "22") (pinfunction "DVDD33_22") (pintype "bidirectional"))
      (node (ref "U$1") (pin "25") (pinfunction "DVDD15_25") (pintype "bidirectional"))
      (node (ref "U$1") (pin "26") (pinfunction "DVDD34_26") (pintype "bidirectional"))
      (node (ref "U$1") (pin "28") (pinfunction "DVDD19_28") (pintype "bidirectional"))
      (node (ref "U$1") (pin "29") (pinfunction "DVDD4_29") (pintype "bidirectional"))
      (node (ref "U$1") (pin "3") (pinfunction "DVDD26_3") (pintype "bidirectional"))
      (node (ref "U$1") (pin "30") (pinfunction "DVDD5_30") (pintype "bidirectional"))
      (node (ref "U$1") (pin "31") (pinfunction "DVDD2_31") (pintype "bidirectional"))
      (node (ref "U$1") (pin "32") (pinfunction "DVDD6_32") (pintype "bidirectional"))
      (node (ref "U$1") (pin "33") (pinfunction "DVDD7_33") (pintype "bidirectional"))
      (node (ref "U$1") (pin "34") (pinfunction "DVDD8_34") (pintype "bidirectional"))
      (node (ref "U$1") (pin "39") (pinfunction "DVDD10_39") (pintype "bidirectional"))
      (node (ref "U$1") (pin "4") (pinfunction "DVDD0_4") (pintype "bidirectional"))
      (node (ref "U$1") (pin "40") (pinfunction "DVDD20_40") (pintype "bidirectional"))
      (node (ref "U$1") (pin "41") (pinfunction "DVDD3_41") (pintype "bidirectional"))
      (node (ref "U$1") (pin "42") (pinfunction "DVDD12_42") (pintype "bidirectional"))
      (node (ref "U$1") (pin "45") (pinfunction "DVDD13_45") (pintype "bidirectional"))
      (node (ref "U$1") (pin "46") (pinfunction "DVDD40_46") (pintype "bidirectional"))
      (node (ref "U$1") (pin "47") (pinfunction "DVDD41_47") (pintype "bidirectional"))
      (node (ref "U$1") (pin "48") (pinfunction "DVDD25_48") (pintype "bidirectional"))
      (node (ref "U$10") (pin "10") (pinfunction "DVDD31_10") (pintype "bidirectional"))
      (node (ref "U$10") (pin "11") (pinfunction "DVDD29_11") (pintype "bidirectional"))
      (node (ref "U$10") (pin "13") (pinfunction "DVDD9_13") (pintype "bidirectional"))
      (node (ref "U$10") (pin "14") (pinfunction "DVDD30_14") (pintype "bidirectional"))
      (node (ref "U$10") (pin "15") (pinfunction "DVDD11_15") (pintype "bidirectional"))
      (node (ref "U$10") (pin "18") (pinfunction "DVDD35_18") (pintype "bidirectional"))
      (node (ref "U$10") (pin "19") (pinfunction "DVDD1_19") (pintype "bidirectional"))
      (node (ref "U$10") (pin "20") (pinfunction "DVDD32_20") (pintype "bidirectional"))
      (node (ref "U$10") (pin "21") (pinfunction "DVDD14_21") (pintype "bidirectional"))
      (node (ref "U$10") (pin "22") (pinfunction "DVDD33_22") (pintype "bidirectional"))
      (node (ref "U$10") (pin "25") (pinfunction "DVDD15_25") (pintype "bidirectional"))
      (node (ref "U$10") (pin "26") (pinfunction "DVDD34_26") (pintype "bidirectional"))
      (node (ref "U$10") (pin "28") (pinfunction "DVDD19_28") (pintype "bidirectional"))
      (node (ref "U$10") (pin "29") (pinfunction "DVDD4_29") (pintype "bidirectional"))
      (node (ref "U$10") (pin "3") (pinfunction "DVDD26_3") (pintype "bidirectional"))
      (node (ref "U$10") (pin "30") (pinfunction "DVDD5_30") (pintype "bidirectional"))
      (node (ref "U$10") (pin "31") (pinfunction "DVDD2_31") (pintype "bidirectional"))
      (node (ref "U$10") (pin "32") (pinfunction "DVDD6_32") (pintype "bidirectional"))
      (node (ref "U$10") (pin "33") (pinfunction "DVDD7_33") (pintype "bidirectional"))
      (node (ref "U$10") (pin "34") (pinfunction "DVDD8_34") (pintype "bidirectional"))
      (node (ref "U$10") (pin "39") (pinfunction "DVDD10_39") (pintype "bidirectional"))
      (node (ref "U$10") (pin "4") (pinfunction "DVDD0_4") (pintype "bidirectional"))
      (node (ref "U$10") (pin "40") (pinfunction "DVDD20_40") (pintype "bidirectional"))
      (node (ref "U$10") (pin "41") (pinfunction "DVDD3_41") (pintype "bidirectional"))
      (node (ref "U$10") (pin "42") (pinfunction "DVDD12_42") (pintype "bidirectional"))
      (node (ref "U$10") (pin "45") (pinfunction "DVDD13_45") (pintype "bidirectional"))
      (node (ref "U$10") (pin "46") (pinfunction "DVDD40_46") (pintype "bidirectional"))
      (node (ref "U$10") (pin "47") (pinfunction "DVDD41_47") (pintype "bidirectional"))
      (node (ref "U$10") (pin "48") (pinfunction "DVDD25_48") (pintype "bidirectional"))
      (node (ref "U$2") (pin "10") (pinfunction "DVDD31_10") (pintype "bidirectional"))
      (node (ref "U$2") (pin "11") (pinfunction "DVDD29_11") (pintype "bidirectional"))
      (node (ref "U$2") (pin "13") (pinfunction "DVDD9_13") (pintype "bidirectional"))
      (node (ref "U$2") (pin "14") (pinfunction "DVDD30_14") (pintype "bidirectional"))
      (node (ref "U$2") (pin "15") (pinfunction "DVDD11_15") (pintype "bidirectional"))
      (node (ref "U$2") (pin "18") (pinfunction "DVDD35_18") (pintype "bidirectional"))
      (node (ref "U$2") (pin "19") (pinfunction "DVDD1_19") (pintype "bidirectional"))
      (node (ref "U$2") (pin "20") (pinfunction "DVDD32_20") (pintype "bidirectional"))
      (node (ref "U$2") (pin "21") (pinfunction "DVDD14_21") (pintype "bidirectional"))
      (node (ref "U$2") (pin "22") (pinfunction "DVDD33_22") (pintype "bidirectional"))
      (node (ref "U$2") (pin "25") (pinfunction "DVDD15_25") (pintype "bidirectional"))
      (node (ref "U$2") (pin "26") (pinfunction "DVDD34_26") (pintype "bidirectional"))
      (node (ref "U$2") (pin "28") (pinfunction "DVDD19_28") (pintype "bidirectional"))
      (node (ref "U$2") (pin "29") (pinfunction "DVDD4_29") (pintype "bidirectional"))
      (node (ref "U$2") (pin "3") (pinfunction "DVDD26_3") (pintype "bidirectional"))
      (node (ref "U$2") (pin "30") (pinfunction "DVDD5_30") (pintype "bidirectional"))
      (node (ref "U$2") (pin "31") (pinfunction "DVDD2_31") (pintype "bidirectional"))
      (node (ref "U$2") (pin "32") (pinfunction "DVDD6_32") (pintype "bidirectional"))
      (node (ref "U$2") (pin "33") (pinfunction "DVDD7_33") (pintype "bidirectional"))
      (node (ref "U$2") (pin "34") (pinfunction "DVDD8_34") (pintype "bidirectional"))
      (node (ref "U$2") (pin "39") (pinfunction "DVDD10_39") (pintype "bidirectional"))
      (node (ref "U$2") (pin "4") (pinfunction "DVDD0_4") (pintype "bidirectional"))
      (node (ref "U$2") (pin "40") (pinfunction "DVDD20_40") (pintype "bidirectional"))
      (node (ref "U$2") (pin "41") (pinfunction "DVDD3_41") (pintype "bidirectional"))
      (node (ref "U$2") (pin "42") (pinfunction "DVDD12_42") (pintype "bidirectional"))
      (node (ref "U$2") (pin "45") (pinfunction "DVDD13_45") (pintype "bidirectional"))
      (node (ref "U$2") (pin "46") (pinfunction "DVDD40_46") (pintype "bidirectional"))
      (node (ref "U$2") (pin "47") (pinfunction "DVDD41_47") (pintype "bidirectional"))
      (node (ref "U$2") (pin "48") (pinfunction "DVDD25_48") (pintype "bidirectional"))
      (node (ref "U$3") (pin "10") (pinfunction "DVDD31_10") (pintype "bidirectional"))
      (node (ref "U$3") (pin "11") (pinfunction "DVDD29_11") (pintype "bidirectional"))
      (node (ref "U$3") (pin "13") (pinfunction "DVDD9_13") (pintype "bidirectional"))
      (node (ref "U$3") (pin "14") (pinfunction "DVDD30_14") (pintype "bidirectional"))
      (node (ref "U$3") (pin "15") (pinfunction "DVDD11_15") (pintype "bidirectional"))
      (node (ref "U$3") (pin "18") (pinfunction "DVDD35_18") (pintype "bidirectional"))
      (node (ref "U$3") (pin "19") (pinfunction "DVDD1_19") (pintype "bidirectional"))
      (node (ref "U$3") (pin "20") (pinfunction "DVDD32_20") (pintype "bidirectional"))
      (node (ref "U$3") (pin "21") (pinfunction "DVDD14_21") (pintype "bidirectional"))
      (node (ref "U$3") (pin "22") (pinfunction "DVDD33_22") (pintype "bidirectional"))
      (node (ref "U$3") (pin "25") (pinfunction "DVDD15_25") (pintype "bidirectional"))
      (node (ref "U$3") (pin "26") (pinfunction "DVDD34_26") (pintype "bidirectional"))
      (node (ref "U$3") (pin "28") (pinfunction "DVDD19_28") (pintype "bidirectional"))
      (node (ref "U$3") (pin "29") (pinfunction "DVDD4_29") (pintype "bidirectional"))
      (node (ref "U$3") (pin "3") (pinfunction "DVDD26_3") (pintype "bidirectional"))
      (node (ref "U$3") (pin "30") (pinfunction "DVDD5_30") (pintype "bidirectional"))
      (node (ref "U$3") (pin "31") (pinfunction "DVDD2_31") (pintype "bidirectional"))
      (node (ref "U$3") (pin "32") (pinfunction "DVDD6_32") (pintype "bidirectional"))
      (node (ref "U$3") (pin "33") (pinfunction "DVDD7_33") (pintype "bidirectional"))
      (node (ref "U$3") (pin "34") (pinfunction "DVDD8_34") (pintype "bidirectional"))
      (node (ref "U$3") (pin "39") (pinfunction "DVDD10_39") (pintype "bidirectional"))
      (node (ref "U$3") (pin "4") (pinfunction "DVDD0_4") (pintype "bidirectional"))
      (node (ref "U$3") (pin "40") (pinfunction "DVDD20_40") (pintype "bidirectional"))
      (node (ref "U$3") (pin "41") (pinfunction "DVDD3_41") (pintype "bidirectional"))
      (node (ref "U$3") (pin "42") (pinfunction "DVDD12_42") (pintype "bidirectional"))
      (node (ref "U$3") (pin "45") (pinfunction "DVDD13_45") (pintype "bidirectional"))
      (node (ref "U$3") (pin "46") (pinfunction "DVDD40_46") (pintype "bidirectional"))
      (node (ref "U$3") (pin "47") (pinfunction "DVDD41_47") (pintype "bidirectional"))
      (node (ref "U$3") (pin "48") (pinfunction "DVDD25_48") (pintype "bidirectional"))
      (node (ref "U$4") (pin "10") (pinfunction "DVDD31_10") (pintype "bidirectional"))
      (node (ref "U$4") (pin "11") (pinfunction "DVDD29_11") (pintype "bidirectional"))
      (node (ref "U$4") (pin "13") (pinfunction "DVDD9_13") (pintype "bidirectional"))
      (node (ref "U$4") (pin "14") (pinfunction "DVDD30_14") (pintype "bidirectional"))
      (node (ref "U$4") (pin "15") (pinfunction "DVDD11_15") (pintype "bidirectional"))
      (node (ref "U$4") (pin "18") (pinfunction "DVDD35_18") (pintype "bidirectional"))
      (node (ref "U$4") (pin "19") (pinfunction "DVDD1_19") (pintype "bidirectional"))
      (node (ref "U$4") (pin "20") (pinfunction "DVDD32_20") (pintype "bidirectional"))
      (node (ref "U$4") (pin "21") (pinfunction "DVDD14_21") (pintype "bidirectional"))
      (node (ref "U$4") (pin "22") (pinfunction "DVDD33_22") (pintype "bidirectional"))
      (node (ref "U$4") (pin "25") (pinfunction "DVDD15_25") (pintype "bidirectional"))
      (node (ref "U$4") (pin "26") (pinfunction "DVDD34_26") (pintype "bidirectional"))
      (node (ref "U$4") (pin "28") (pinfunction "DVDD19_28") (pintype "bidirectional"))
      (node (ref "U$4") (pin "29") (pinfunction "DVDD4_29") (pintype "bidirectional"))
      (node (ref "U$4") (pin "3") (pinfunction "DVDD26_3") (pintype "bidirectional"))
      (node (ref "U$4") (pin "30") (pinfunction "DVDD5_30") (pintype "bidirectional"))
      (node (ref "U$4") (pin "31") (pinfunction "DVDD2_31") (pintype "bidirectional"))
      (node (ref "U$4") (pin "32") (pinfunction "DVDD6_32") (pintype "bidirectional"))
      (node (ref "U$4") (pin "33") (pinfunction "DVDD7_33") (pintype "bidirectional"))
      (node (ref "U$4") (pin "34") (pinfunction "DVDD8_34") (pintype "bidirectional"))
      (node (ref "U$4") (pin "39") (pinfunction "DVDD10_39") (pintype "bidirectional"))
      (node (ref "U$4") (pin "4") (pinfunction "DVDD0_4") (pintype "bidirectional"))
      (node (ref "U$4") (pin "40") (pinfunction "DVDD20_40") (pintype "bidirectional"))
      (node (ref "U$4") (pin "41") (pinfunction "DVDD3_41") (pintype "bidirectional"))
      (node (ref "U$4") (pin "42") (pinfunction "DVDD12_42") (pintype "bidirectional"))
      (node (ref "U$4") (pin "45") (pinfunction "DVDD13_45") (pintype "bidirectional"))
      (node (ref "U$4") (pin "46") (pinfunction "DVDD40_46") (pintype "bidirectional"))
      (node (ref "U$4") (pin "47") (pinfunction "DVDD41_47") (pintype "bidirectional"))
      (node (ref "U$4") (pin "48") (pinfunction "DVDD25_48") (pintype "bidirectional"))
      (node (ref "U$5") (pin "10") (pinfunction "DVDD31_10") (pintype "bidirectional"))
      (node (ref "U$5") (pin "11") (pinfunction "DVDD29_11") (pintype "bidirectional"))
      (node (ref "U$5") (pin "13") (pinfunction "DVDD9_13") (pintype "bidirectional"))
      (node (ref "U$5") (pin "14") (pinfunction "DVDD30_14") (pintype "bidirectional"))
      (node (ref "U$5") (pin "15") (pinfunction "DVDD11_15") (pintype "bidirectional"))
      (node (ref "U$5") (pin "18") (pinfunction "DVDD35_18") (pintype "bidirectional"))
      (node (ref "U$5") (pin "19") (pinfunction "DVDD1_19") (pintype "bidirectional"))
      (node (ref "U$5") (pin "20") (pinfunction "DVDD32_20") (pintype "bidirectional"))
      (node (ref "U$5") (pin "21") (pinfunction "DVDD14_21") (pintype "bidirectional"))
      (node (ref "U$5") (pin "22") (pinfunction "DVDD33_22") (pintype "bidirectional"))
      (node (ref "U$5") (pin "25") (pinfunction "DVDD15_25") (pintype "bidirectional"))
      (node (ref "U$5") (pin "26") (pinfunction "DVDD34_26") (pintype "bidirectional"))
      (node (ref "U$5") (pin "28") (pinfunction "DVDD19_28") (pintype "bidirectional"))
      (node (ref "U$5") (pin "29") (pinfunction "DVDD4_29") (pintype "bidirectional"))
      (node (ref "U$5") (pin "3") (pinfunction "DVDD26_3") (pintype "bidirectional"))
      (node (ref "U$5") (pin "30") (pinfunction "DVDD5_30") (pintype "bidirectional"))
      (node (ref "U$5") (pin "31") (pinfunction "DVDD2_31") (pintype "bidirectional"))
      (node (ref "U$5") (pin "32") (pinfunction "DVDD6_32") (pintype "bidirectional"))
      (node (ref "U$5") (pin "33") (pinfunction "DVDD7_33") (pintype "bidirectional"))
      (node (ref "U$5") (pin "34") (pinfunction "DVDD8_34") (pintype "bidirectional"))
      (node (ref "U$5") (pin "39") (pinfunction "DVDD10_39") (pintype "bidirectional"))
      (node (ref "U$5") (pin "4") (pinfunction "DVDD0_4") (pintype "bidirectional"))
      (node (ref "U$5") (pin "40") (pinfunction "DVDD20_40") (pintype "bidirectional"))
      (node (ref "U$5") (pin "41") (pinfunction "DVDD3_41") (pintype "bidirectional"))
      (node (ref "U$5") (pin "42") (pinfunction "DVDD12_42") (pintype "bidirectional"))
      (node (ref "U$5") (pin "45") (pinfunction "DVDD13_45") (pintype "bidirectional"))
      (node (ref "U$5") (pin "46") (pinfunction "DVDD40_46") (pintype "bidirectional"))
      (node (ref "U$5") (pin "47") (pinfunction "DVDD41_47") (pintype "bidirectional"))
      (node (ref "U$5") (pin "48") (pinfunction "DVDD25_48") (pintype "bidirectional"))
      (node (ref "U$6") (pin "10") (pinfunction "DVDD31_10") (pintype "bidirectional"))
      (node (ref "U$6") (pin "11") (pinfunction "DVDD29_11") (pintype "bidirectional"))
      (node (ref "U$6") (pin "13") (pinfunction "DVDD9_13") (pintype "bidirectional"))
      (node (ref "U$6") (pin "14") (pinfunction "DVDD30_14") (pintype "bidirectional"))
      (node (ref "U$6") (pin "15") (pinfunction "DVDD11_15") (pintype "bidirectional"))
      (node (ref "U$6") (pin "18") (pinfunction "DVDD35_18") (pintype "bidirectional"))
      (node (ref "U$6") (pin "19") (pinfunction "DVDD1_19") (pintype "bidirectional"))
      (node (ref "U$6") (pin "20") (pinfunction "DVDD32_20") (pintype "bidirectional"))
      (node (ref "U$6") (pin "21") (pinfunction "DVDD14_21") (pintype "bidirectional"))
      (node (ref "U$6") (pin "22") (pinfunction "DVDD33_22") (pintype "bidirectional"))
      (node (ref "U$6") (pin "25") (pinfunction "DVDD15_25") (pintype "bidirectional"))
      (node (ref "U$6") (pin "26") (pinfunction "DVDD34_26") (pintype "bidirectional"))
      (node (ref "U$6") (pin "28") (pinfunction "DVDD19_28") (pintype "bidirectional"))
      (node (ref "U$6") (pin "29") (pinfunction "DVDD4_29") (pintype "bidirectional"))
      (node (ref "U$6") (pin "3") (pinfunction "DVDD26_3") (pintype "bidirectional"))
      (node (ref "U$6") (pin "30") (pinfunction "DVDD5_30") (pintype "bidirectional"))
      (node (ref "U$6") (pin "31") (pinfunction "DVDD2_31") (pintype "bidirectional"))
      (node (ref "U$6") (pin "32") (pinfunction "DVDD6_32") (pintype "bidirectional"))
      (node (ref "U$6") (pin "33") (pinfunction "DVDD7_33") (pintype "bidirectional"))
      (node (ref "U$6") (pin "34") (pinfunction "DVDD8_34") (pintype "bidirectional"))
      (node (ref "U$6") (pin "39") (pinfunction "DVDD10_39") (pintype "bidirectional"))
      (node (ref "U$6") (pin "4") (pinfunction "DVDD0_4") (pintype "bidirectional"))
      (node (ref "U$6") (pin "40") (pinfunction "DVDD20_40") (pintype "bidirectional"))
      (node (ref "U$6") (pin "41") (pinfunction "DVDD3_41") (pintype "bidirectional"))
      (node (ref "U$6") (pin "42") (pinfunction "DVDD12_42") (pintype "bidirectional"))
      (node (ref "U$6") (pin "45") (pinfunction "DVDD13_45") (pintype "bidirectional"))
      (node (ref "U$6") (pin "46") (pinfunction "DVDD40_46") (pintype "bidirectional"))
      (node (ref "U$6") (pin "47") (pinfunction "DVDD41_47") (pintype "bidirectional"))
      (node (ref "U$6") (pin "48") (pinfunction "DVDD25_48") (pintype "bidirectional"))
      (node (ref "U$7") (pin "10") (pinfunction "DVDD31_10") (pintype "bidirectional"))
      (node (ref "U$7") (pin "11") (pinfunction "DVDD29_11") (pintype "bidirectional"))
      (node (ref "U$7") (pin "13") (pinfunction "DVDD9_13") (pintype "bidirectional"))
      (node (ref "U$7") (pin "14") (pinfunction "DVDD30_14") (pintype "bidirectional"))
      (node (ref "U$7") (pin "15") (pinfunction "DVDD11_15") (pintype "bidirectional"))
      (node (ref "U$7") (pin "18") (pinfunction "DVDD35_18") (pintype "bidirectional"))
      (node (ref "U$7") (pin "19") (pinfunction "DVDD1_19") (pintype "bidirectional"))
      (node (ref "U$7") (pin "20") (pinfunction "DVDD32_20") (pintype "bidirectional"))
      (node (ref "U$7") (pin "21") (pinfunction "DVDD14_21") (pintype "bidirectional"))
      (node (ref "U$7") (pin "22") (pinfunction "DVDD33_22") (pintype "bidirectional"))
      (node (ref "U$7") (pin "25") (pinfunction "DVDD15_25") (pintype "bidirectional"))
      (node (ref "U$7") (pin "26") (pinfunction "DVDD34_26") (pintype "bidirectional"))
      (node (ref "U$7") (pin "28") (pinfunction "DVDD19_28") (pintype "bidirectional"))
      (node (ref "U$7") (pin "29") (pinfunction "DVDD4_29") (pintype "bidirectional"))
      (node (ref "U$7") (pin "3") (pinfunction "DVDD26_3") (pintype "bidirectional"))
      (node (ref "U$7") (pin "30") (pinfunction "DVDD5_30") (pintype "bidirectional"))
      (node (ref "U$7") (pin "31") (pinfunction "DVDD2_31") (pintype "bidirectional"))
      (node (ref "U$7") (pin "32") (pinfunction "DVDD6_32") (pintype "bidirectional"))
      (node (ref "U$7") (pin "33") (pinfunction "DVDD7_33") (pintype "bidirectional"))
      (node (ref "U$7") (pin "34") (pinfunction "DVDD8_34") (pintype "bidirectional"))
      (node (ref "U$7") (pin "39") (pinfunction "DVDD10_39") (pintype "bidirectional"))
      (node (ref "U$7") (pin "4") (pinfunction "DVDD0_4") (pintype "bidirectional"))
      (node (ref "U$7") (pin "40") (pinfunction "DVDD20_40") (pintype "bidirectional"))
      (node (ref "U$7") (pin "41") (pinfunction "DVDD3_41") (pintype "bidirectional"))
      (node (ref "U$7") (pin "42") (pinfunction "DVDD12_42") (pintype "bidirectional"))
      (node (ref "U$7") (pin "45") (pinfunction "DVDD13_45") (pintype "bidirectional"))
      (node (ref "U$7") (pin "46") (pinfunction "DVDD40_46") (pintype "bidirectional"))
      (node (ref "U$7") (pin "47") (pinfunction "DVDD41_47") (pintype "bidirectional"))
      (node (ref "U$7") (pin "48") (pinfunction "DVDD25_48") (pintype "bidirectional"))
      (node (ref "U$8") (pin "10") (pinfunction "DVDD31_10") (pintype "bidirectional"))
      (node (ref "U$8") (pin "11") (pinfunction "DVDD29_11") (pintype "bidirectional"))
      (node (ref "U$8") (pin "13") (pinfunction "DVDD9_13") (pintype "bidirectional"))
      (node (ref "U$8") (pin "14") (pinfunction "DVDD30_14") (pintype "bidirectional"))
      (node (ref "U$8") (pin "15") (pinfunction "DVDD11_15") (pintype "bidirectional"))
      (node (ref "U$8") (pin "18") (pinfunction "DVDD35_18") (pintype "bidirectional"))
      (node (ref "U$8") (pin "19") (pinfunction "DVDD1_19") (pintype "bidirectional"))
      (node (ref "U$8") (pin "20") (pinfunction "DVDD32_20") (pintype "bidirectional"))
      (node (ref "U$8") (pin "21") (pinfunction "DVDD14_21") (pintype "bidirectional"))
      (node (ref "U$8") (pin "22") (pinfunction "DVDD33_22") (pintype "bidirectional"))
      (node (ref "U$8") (pin "25") (pinfunction "DVDD15_25") (pintype "bidirectional"))
      (node (ref "U$8") (pin "26") (pinfunction "DVDD34_26") (pintype "bidirectional"))
      (node (ref "U$8") (pin "28") (pinfunction "DVDD19_28") (pintype "bidirectional"))
      (node (ref "U$8") (pin "29") (pinfunction "DVDD4_29") (pintype "bidirectional"))
      (node (ref "U$8") (pin "3") (pinfunction "DVDD26_3") (pintype "bidirectional"))
      (node (ref "U$8") (pin "30") (pinfunction "DVDD5_30") (pintype "bidirectional"))
      (node (ref "U$8") (pin "31") (pinfunction "DVDD2_31") (pintype "bidirectional"))
      (node (ref "U$8") (pin "32") (pinfunction "DVDD6_32") (pintype "bidirectional"))
      (node (ref "U$8") (pin "33") (pinfunction "DVDD7_33") (pintype "bidirectional"))
      (node (ref "U$8") (pin "34") (pinfunction "DVDD8_34") (pintype "bidirectional"))
      (node (ref "U$8") (pin "39") (pinfunction "DVDD10_39") (pintype "bidirectional"))
      (node (ref "U$8") (pin "4") (pinfunction "DVDD0_4") (pintype "bidirectional"))
      (node (ref "U$8") (pin "40") (pinfunction "DVDD20_40") (pintype "bidirectional"))
      (node (ref "U$8") (pin "41") (pinfunction "DVDD3_41") (pintype "bidirectional"))
      (node (ref "U$8") (pin "42") (pinfunction "DVDD12_42") (pintype "bidirectional"))
      (node (ref "U$8") (pin "45") (pinfunction "DVDD13_45") (pintype "bidirectional"))
      (node (ref "U$8") (pin "46") (pinfunction "DVDD40_46") (pintype "bidirectional"))
      (node (ref "U$8") (pin "47") (pinfunction "DVDD41_47") (pintype "bidirectional"))
      (node (ref "U$8") (pin "48") (pinfunction "DVDD25_48") (pintype "bidirectional"))
      (node (ref "U$9") (pin "10") (pinfunction "DVDD31_10") (pintype "bidirectional"))
      (node (ref "U$9") (pin "11") (pinfunction "DVDD29_11") (pintype "bidirectional"))
      (node (ref "U$9") (pin "13") (pinfunction "DVDD9_13") (pintype "bidirectional"))
      (node (ref "U$9") (pin "14") (pinfunction "DVDD30_14") (pintype "bidirectional"))
      (node (ref "U$9") (pin "15") (pinfunction "DVDD11_15") (pintype "bidirectional"))
      (node (ref "U$9") (pin "18") (pinfunction "DVDD35_18") (pintype "bidirectional"))
      (node (ref "U$9") (pin "19") (pinfunction "DVDD1_19") (pintype "bidirectional"))
      (node (ref "U$9") (pin "20") (pinfunction "DVDD32_20") (pintype "bidirectional"))
      (node (ref "U$9") (pin "21") (pinfunction "DVDD14_21") (pintype "bidirectional"))
      (node (ref "U$9") (pin "22") (pinfunction "DVDD33_22") (pintype "bidirectional"))
      (node (ref "U$9") (pin "25") (pinfunction "DVDD15_25") (pintype "bidirectional"))
      (node (ref "U$9") (pin "26") (pinfunction "DVDD34_26") (pintype "bidirectional"))
      (node (ref "U$9") (pin "28") (pinfunction "DVDD19_28") (pintype "bidirectional"))
      (node (ref "U$9") (pin "29") (pinfunction "DVDD4_29") (pintype "bidirectional"))
      (node (ref "U$9") (pin "3") (pinfunction "DVDD26_3") (pintype "bidirectional"))
      (node (ref "U$9") (pin "30") (pinfunction "DVDD5_30") (pintype "bidirectional"))
      (node (ref "U$9") (pin "31") (pinfunction "DVDD2_31") (pintype "bidirectional"))
      (node (ref "U$9") (pin "32") (pinfunction "DVDD6_32") (pintype "bidirectional"))
      (node (ref "U$9") (pin "33") (pinfunction "DVDD7_33") (pintype "bidirectional"))
      (node (ref "U$9") (pin "34") (pinfunction "DVDD8_34") (pintype "bidirectional"))
      (node (ref "U$9") (pin "39") (pinfunction "DVDD10_39") (pintype "bidirectional"))
      (node (ref "U$9") (pin "4") (pinfunction "DVDD0_4") (pintype "bidirectional"))
      (node (ref "U$9") (pin "40") (pinfunction "DVDD20_40") (pintype "bidirectional"))
      (node (ref "U$9") (pin "41") (pinfunction "DVDD3_41") (pintype "bidirectional"))
      (node (ref "U$9") (pin "42") (pinfunction "DVDD12_42") (pintype "bidirectional"))
      (node (ref "U$9") (pin "45") (pinfunction "DVDD13_45") (pintype "bidirectional"))
      (node (ref "U$9") (pin "46") (pinfunction "DVDD40_46") (pintype "bidirectional"))
      (node (ref "U$9") (pin "47") (pinfunction "DVDD41_47") (pintype "bidirectional"))
      (node (ref "U$9") (pin "48") (pinfunction "DVDD25_48") (pintype "bidirectional"))
    )
    (net (code "42") (name "GND") (class "Default")
      (node (ref "C1") (pin "1") (pinfunction "1_1") (pintype "passive"))
      (node (ref "C10") (pin "2") (pinfunction "2_2") (pintype "passive"))
      (node (ref "C100") (pin "2") (pinfunction "2_2") (pintype "passive"))
      (node (ref "C101") (pin "2") (pinfunction "2_2") (pintype "passive"))
      (node (ref "C102") (pin "2") (pinfunction "2_2") (pintype "passive"))
      (node (ref "C103") (pin "2") (pinfunction "2_2") (pintype "passive"))
      (node (ref "C104") (pin "2") (pinfunction "2_2") (pintype "passive"))
      (node (ref "C105") (pin "2") (pinfunction "2_2") (pintype "passive"))
      (node (ref "C106") (pin "2") (pinfunction "2_2") (pintype "passive"))
      (node (ref "C107") (pin "2") (pinfunction "2_2") (pintype "passive"))
      (node (ref "C108") (pin "2") (pinfunction "2_2") (pintype "passive"))
      (node (ref "C109") (pin "1") (pinfunction "1_1") (pintype "passive"))
      (node (ref "C11") (pin "2") (pinfunction "2_2") (pintype "passive"))
      (node (ref "C110") (pin "1") (pinfunction "1_1") (pintype "passive"))
      (node (ref "C111") (pin "2") (pinfunction "2_2") (pintype "passive"))
      (node (ref "C112") (pin "2") (pinfunction "2_2") (pintype "passive"))
      (node (ref "C113") (pin "2") (pinfunction "2_2") (pintype "passive"))
      (node (ref "C114") (pin "2") (pinfunction "2_2") (pintype "passive"))
      (node (ref "C115") (pin "2") (pinfunction "2_2") (pintype "passive"))
      (node (ref "C116") (pin "2") (pinfunction "2_2") (pintype "passive"))
      (node (ref "C117") (pin "2") (pinfunction "2_2") (pintype "passive"))
      (node (ref "C118") (pin "2") (pinfunction "2_2") (pintype "passive"))
      (node (ref "C119") (pin "2") (pinfunction "2_2") (pintype "passive"))
      (node (ref "C12") (pin "2") (pinfunction "2_2") (pintype "passive"))
      (node (ref "C120") (pin "2") (pinfunction "2_2") (pintype "passive"))
      (node (ref "C13") (pin "1") (pinfunction "1_1") (pintype "passive"))
      (node (ref "C14") (pin "1") (pinfunction "1_1") (pintype "passive"))
      (node (ref "C15") (pin "2") (pinfunction "2_2") (pintype "passive"))
      (node (ref "C16") (pin "2") (pinfunction "2_2") (pintype "passive"))
      (node (ref "C17") (pin "2") (pinfunction "2_2") (pintype "passive"))
      (node (ref "C18") (pin "2") (pinfunction "2_2") (pintype "passive"))
      (node (ref "C19") (pin "2") (pinfunction "2_2") (pintype "passive"))
      (node (ref "C2") (pin "1") (pinfunction "1_1") (pintype "passive"))
      (node (ref "C20") (pin "2") (pinfunction "2_2") (pintype "passive"))
      (node (ref "C21") (pin "2") (pinfunction "2_2") (pintype "passive"))
      (node (ref "C22") (pin "2") (pinfunction "2_2") (pintype "passive"))
      (node (ref "C23") (pin "2") (pinfunction "2_2") (pintype "passive"))
      (node (ref "C24") (pin "2") (pinfunction "2_2") (pintype "passive"))
      (node (ref "C25") (pin "1") (pinfunction "1_1") (pintype "passive"))
      (node (ref "C26") (pin "1") (pinfunction "1_1") (pintype "passive"))
      (node (ref "C27") (pin "2") (pinfunction "2_2") (pintype "passive"))
      (node (ref "C28") (pin "2") (pinfunction "2_2") (pintype "passive"))
      (node (ref "C29") (pin "2") (pinfunction "2_2") (pintype "passive"))
      (node (ref "C3") (pin "2") (pinfunction "2_2") (pintype "passive"))
      (node (ref "C30") (pin "2") (pinfunction "2_2") (pintype "passive"))
      (node (ref "C31") (pin "2") (pinfunction "2_2") (pintype "passive"))
      (node (ref "C32") (pin "2") (pinfunction "2_2") (pintype "passive"))
      (node (ref "C33") (pin "2") (pinfunction "2_2") (pintype "passive"))
      (node (ref "C34") (pin "2") (pinfunction "2_2") (pintype "passive"))
      (node (ref "C35") (pin "2") (pinfunction "2_2") (pintype "passive"))
      (node (ref "C36") (pin "2") (pinfunction "2_2") (pintype "passive"))
      (node (ref "C37") (pin "1") (pinfunction "1_1") (pintype "passive"))
      (node (ref "C38") (pin "1") (pinfunction "1_1") (pintype "passive"))
      (node (ref "C39") (pin "2") (pinfunction "2_2") (pintype "passive"))
      (node (ref "C4") (pin "2") (pinfunction "2_2") (pintype "passive"))
      (node (ref "C40") (pin "2") (pinfunction "2_2") (pintype "passive"))
      (node (ref "C41") (pin "2") (pinfunction "2_2") (pintype "passive"))
      (node (ref "C42") (pin "2") (pinfunction "2_2") (pintype "passive"))
      (node (ref "C43") (pin "2") (pinfunction "2_2") (pintype "passive"))
      (node (ref "C44") (pin "2") (pinfunction "2_2") (pintype "passive"))
      (node (ref "C45") (pin "2") (pinfunction "2_2") (pintype "passive"))
      (node (ref "C46") (pin "2") (pinfunction "2_2") (pintype "passive"))
      (node (ref "C47") (pin "2") (pinfunction "2_2") (pintype "passive"))
      (node (ref "C48") (pin "2") (pinfunction "2_2") (pintype "passive"))
      (node (ref "C49") (pin "1") (pinfunction "1_1") (pintype "passive"))
      (node (ref "C5") (pin "2") (pinfunction "2_2") (pintype "passive"))
      (node (ref "C50") (pin "1") (pinfunction "1_1") (pintype "passive"))
      (node (ref "C51") (pin "2") (pinfunction "2_2") (pintype "passive"))
      (node (ref "C52") (pin "2") (pinfunction "2_2") (pintype "passive"))
      (node (ref "C53") (pin "2") (pinfunction "2_2") (pintype "passive"))
      (node (ref "C54") (pin "2") (pinfunction "2_2") (pintype "passive"))
      (node (ref "C55") (pin "2") (pinfunction "2_2") (pintype "passive"))
      (node (ref "C56") (pin "2") (pinfunction "2_2") (pintype "passive"))
      (node (ref "C57") (pin "2") (pinfunction "2_2") (pintype "passive"))
      (node (ref "C58") (pin "2") (pinfunction "2_2") (pintype "passive"))
      (node (ref "C59") (pin "2") (pinfunction "2_2") (pintype "passive"))
      (node (ref "C6") (pin "2") (pinfunction "2_2") (pintype "passive"))
      (node (ref "C60") (pin "2") (pinfunction "2_2") (pintype "passive"))
      (node (ref "C61") (pin "1") (pinfunction "1_1") (pintype "passive"))
      (node (ref "C62") (pin "1") (pinfunction "1_1") (pintype "passive"))
      (node (ref "C63") (pin "2") (pinfunction "2_2") (pintype "passive"))
      (node (ref "C64") (pin "2") (pinfunction "2_2") (pintype "passive"))
      (node (ref "C65") (pin "2") (pinfunction "2_2") (pintype "passive"))
      (node (ref "C66") (pin "2") (pinfunction "2_2") (pintype "passive"))
      (node (ref "C67") (pin "2") (pinfunction "2_2") (pintype "passive"))
      (node (ref "C68") (pin "2") (pinfunction "2_2") (pintype "passive"))
      (node (ref "C69") (pin "2") (pinfunction "2_2") (pintype "passive"))
      (node (ref "C7") (pin "2") (pinfunction "2_2") (pintype "passive"))
      (node (ref "C70") (pin "2") (pinfunction "2_2") (pintype "passive"))
      (node (ref "C71") (pin "2") (pinfunction "2_2") (pintype "passive"))
      (node (ref "C72") (pin "2") (pinfunction "2_2") (pintype "passive"))
      (node (ref "C73") (pin "1") (pinfunction "1_1") (pintype "passive"))
      (node (ref "C74") (pin "1") (pinfunction "1_1") (pintype "passive"))
      (node (ref "C75") (pin "2") (pinfunction "2_2") (pintype "passive"))
      (node (ref "C76") (pin "2") (pinfunction "2_2") (pintype "passive"))
      (node (ref "C77") (pin "2") (pinfunction "2_2") (pintype "passive"))
      (node (ref "C78") (pin "2") (pinfunction "2_2") (pintype "passive"))
      (node (ref "C79") (pin "2") (pinfunction "2_2") (pintype "passive"))
      (node (ref "C8") (pin "2") (pinfunction "2_2") (pintype "passive"))
      (node (ref "C80") (pin "2") (pinfunction "2_2") (pintype "passive"))
      (node (ref "C81") (pin "2") (pinfunction "2_2") (pintype "passive"))
      (node (ref "C82") (pin "2") (pinfunction "2_2") (pintype "passive"))
      (node (ref "C83") (pin "2") (pinfunction "2_2") (pintype "passive"))
      (node (ref "C84") (pin "2") (pinfunction "2_2") (pintype "passive"))
      (node (ref "C85") (pin "1") (pinfunction "1_1") (pintype "passive"))
      (node (ref "C86") (pin "1") (pinfunction "1_1") (pintype "passive"))
      (node (ref "C87") (pin "2") (pinfunction "2_2") (pintype "passive"))
      (node (ref "C88") (pin "2") (pinfunction "2_2") (pintype "passive"))
      (node (ref "C89") (pin "2") (pinfunction "2_2") (pintype "passive"))
      (node (ref "C9") (pin "2") (pinfunction "2_2") (pintype "passive"))
      (node (ref "C90") (pin "2") (pinfunction "2_2") (pintype "passive"))
      (node (ref "C91") (pin "2") (pinfunction "2_2") (pintype "passive"))
      (node (ref "C92") (pin "2") (pinfunction "2_2") (pintype "passive"))
      (node (ref "C93") (pin "2") (pinfunction "2_2") (pintype "passive"))
      (node (ref "C94") (pin "2") (pinfunction "2_2") (pintype "passive"))
      (node (ref "C95") (pin "2") (pinfunction "2_2") (pintype "passive"))
      (node (ref "C96") (pin "2") (pinfunction "2_2") (pintype "passive"))
      (node (ref "C97") (pin "1") (pinfunction "1_1") (pintype "passive"))
      (node (ref "C98") (pin "1") (pinfunction "1_1") (pintype "passive"))
      (node (ref "C99") (pin "2") (pinfunction "2_2") (pintype "passive"))
      (node (ref "PL1") (pin "14") (pinfunction "S_14") (pintype "passive"))
      (node (ref "PL1") (pin "3") (pinfunction "S_3") (pintype "passive"))
      (node (ref "U$1") (pin "12") (pinfunction "DVSS4_12") (pintype "bidirectional"))
      (node (ref "U$1") (pin "23") (pinfunction "OVSS1_23") (pintype "bidirectional"))
      (node (ref "U$1") (pin "27") (pinfunction "DVSS5_27") (pintype "bidirectional"))
      (node (ref "U$1") (pin "38") (pinfunction "OVSS0_38") (pintype "bidirectional"))
      (node (ref "U$1") (pin "49") (pinfunction "GND_49") (pintype "bidirectional"))
      (node (ref "U$1") (pin "5") (pinfunction "VSSA_PLL_5") (pintype "bidirectional"))
      (node (ref "U$1") (pin "8") (pinfunction "VSS_PLL_8") (pintype "bidirectional"))
      (node (ref "U$10") (pin "12") (pinfunction "DVSS4_12") (pintype "bidirectional"))
      (node (ref "U$10") (pin "23") (pinfunction "OVSS1_23") (pintype "bidirectional"))
      (node (ref "U$10") (pin "27") (pinfunction "DVSS5_27") (pintype "bidirectional"))
      (node (ref "U$10") (pin "38") (pinfunction "OVSS0_38") (pintype "bidirectional"))
      (node (ref "U$10") (pin "49") (pinfunction "GND_49") (pintype "bidirectional"))
      (node (ref "U$10") (pin "5") (pinfunction "VSSA_PLL_5") (pintype "bidirectional"))
      (node (ref "U$10") (pin "8") (pinfunction "VSS_PLL_8") (pintype "bidirectional"))
      (node (ref "U$11") (pin "4") (pinfunction "G_4") (pintype "bidirectional"))
      (node (ref "U$12") (pin "4") (pinfunction "G_4") (pintype "bidirectional"))
      (node (ref "U$13") (pin "4") (pinfunction "G_4") (pintype "bidirectional"))
      (node (ref "U$2") (pin "12") (pinfunction "DVSS4_12") (pintype "bidirectional"))
      (node (ref "U$2") (pin "23") (pinfunction "OVSS1_23") (pintype "bidirectional"))
      (node (ref "U$2") (pin "27") (pinfunction "DVSS5_27") (pintype "bidirectional"))
      (node (ref "U$2") (pin "38") (pinfunction "OVSS0_38") (pintype "bidirectional"))
      (node (ref "U$2") (pin "49") (pinfunction "GND_49") (pintype "bidirectional"))
      (node (ref "U$2") (pin "5") (pinfunction "VSSA_PLL_5") (pintype "bidirectional"))
      (node (ref "U$2") (pin "8") (pinfunction "VSS_PLL_8") (pintype "bidirectional"))
      (node (ref "U$3") (pin "12") (pinfunction "DVSS4_12") (pintype "bidirectional"))
      (node (ref "U$3") (pin "23") (pinfunction "OVSS1_23") (pintype "bidirectional"))
      (node (ref "U$3") (pin "27") (pinfunction "DVSS5_27") (pintype "bidirectional"))
      (node (ref "U$3") (pin "38") (pinfunction "OVSS0_38") (pintype "bidirectional"))
      (node (ref "U$3") (pin "49") (pinfunction "GND_49") (pintype "bidirectional"))
      (node (ref "U$3") (pin "5") (pinfunction "VSSA_PLL_5") (pintype "bidirectional"))
      (node (ref "U$3") (pin "8") (pinfunction "VSS_PLL_8") (pintype "bidirectional"))
      (node (ref "U$4") (pin "12") (pinfunction "DVSS4_12") (pintype "bidirectional"))
      (node (ref "U$4") (pin "23") (pinfunction "OVSS1_23") (pintype "bidirectional"))
      (node (ref "U$4") (pin "27") (pinfunction "DVSS5_27") (pintype "bidirectional"))
      (node (ref "U$4") (pin "38") (pinfunction "OVSS0_38") (pintype "bidirectional"))
      (node (ref "U$4") (pin "49") (pinfunction "GND_49") (pintype "bidirectional"))
      (node (ref "U$4") (pin "5") (pinfunction "VSSA_PLL_5") (pintype "bidirectional"))
      (node (ref "U$4") (pin "8") (pinfunction "VSS_PLL_8") (pintype "bidirectional"))
      (node (ref "U$5") (pin "12") (pinfunction "DVSS4_12") (pintype "bidirectional"))
      (node (ref "U$5") (pin "23") (pinfunction "OVSS1_23") (pintype "bidirectional"))
      (node (ref "U$5") (pin "27") (pinfunction "DVSS5_27") (pintype "bidirectional"))
      (node (ref "U$5") (pin "38") (pinfunction "OVSS0_38") (pintype "bidirectional"))
      (node (ref "U$5") (pin "49") (pinfunction "GND_49") (pintype "bidirectional"))
      (node (ref "U$5") (pin "5") (pinfunction "VSSA_PLL_5") (pintype "bidirectional"))
      (node (ref "U$5") (pin "8") (pinfunction "VSS_PLL_8") (pintype "bidirectional"))
      (node (ref "U$6") (pin "12") (pinfunction "DVSS4_12") (pintype "bidirectional"))
      (node (ref "U$6") (pin "23") (pinfunction "OVSS1_23") (pintype "bidirectional"))
      (node (ref "U$6") (pin "27") (pinfunction "DVSS5_27") (pintype "bidirectional"))
      (node (ref "U$6") (pin "38") (pinfunction "OVSS0_38") (pintype "bidirectional"))
      (node (ref "U$6") (pin "49") (pinfunction "GND_49") (pintype "bidirectional"))
      (node (ref "U$6") (pin "5") (pinfunction "VSSA_PLL_5") (pintype "bidirectional"))
      (node (ref "U$6") (pin "8") (pinfunction "VSS_PLL_8") (pintype "bidirectional"))
      (node (ref "U$7") (pin "12") (pinfunction "DVSS4_12") (pintype "bidirectional"))
      (node (ref "U$7") (pin "23") (pinfunction "OVSS1_23") (pintype "bidirectional"))
      (node (ref "U$7") (pin "27") (pinfunction "DVSS5_27") (pintype "bidirectional"))
      (node (ref "U$7") (pin "38") (pinfunction "OVSS0_38") (pintype "bidirectional"))
      (node (ref "U$7") (pin "49") (pinfunction "GND_49") (pintype "bidirectional"))
      (node (ref "U$7") (pin "5") (pinfunction "VSSA_PLL_5") (pintype "bidirectional"))
      (node (ref "U$7") (pin "8") (pinfunction "VSS_PLL_8") (pintype "bidirectional"))
      (node (ref "U$8") (pin "12") (pinfunction "DVSS4_12") (pintype "bidirectional"))
      (node (ref "U$8") (pin "23") (pinfunction "OVSS1_23") (pintype "bidirectional"))
      (node (ref "U$8") (pin "27") (pinfunction "DVSS5_27") (pintype "bidirectional"))
      (node (ref "U$8") (pin "38") (pinfunction "OVSS0_38") (pintype "bidirectional"))
      (node (ref "U$8") (pin "49") (pinfunction "GND_49") (pintype "bidirectional"))
      (node (ref "U$8") (pin "5") (pinfunction "VSSA_PLL_5") (pintype "bidirectional"))
      (node (ref "U$8") (pin "8") (pinfunction "VSS_PLL_8") (pintype "bidirectional"))
      (node (ref "U$9") (pin "12") (pinfunction "DVSS4_12") (pintype "bidirectional"))
      (node (ref "U$9") (pin "23") (pinfunction "OVSS1_23") (pintype "bidirectional"))
      (node (ref "U$9") (pin "27") (pinfunction "DVSS5_27") (pintype "bidirectional"))
      (node (ref "U$9") (pin "38") (pinfunction "OVSS0_38") (pintype "bidirectional"))
      (node (ref "U$9") (pin "49") (pinfunction "GND_49") (pintype "bidirectional"))
      (node (ref "U$9") (pin "5") (pinfunction "VSSA_PLL_5") (pintype "bidirectional"))
      (node (ref "U$9") (pin "8") (pinfunction "VSS_PLL_8") (pintype "bidirectional"))
    )
    (net (code "43") (name "Net-(U$1-CORE_CLOCKOUT)") (class "Default")
      (node (ref "C_CLKOUT") (pin "TP") (pinfunction "TP_TP") (pintype "input"))
      (node (ref "U$1") (pin "43") (pinfunction "CORE_CLOCKOUT_43") (pintype "bidirectional"))
    )
    (net (code "44") (name "Net-(U$1-VDDA_PLL)") (class "Default")
      (node (ref "C2") (pin "2") (pinfunction "2_2") (pintype "passive"))
      (node (ref "R1") (pin "2") (pinfunction "2_2") (pintype "passive"))
      (node (ref "U$1") (pin "6") (pinfunction "VDDA_PLL_6") (pintype "bidirectional"))
      (node (ref "U$1") (pin "7") (pinfunction "VDD_PLL_7") (pintype "bidirectional"))
    )
    (net (code "45") (name "Net-(U$2-CORE_CLOCKOUT)") (class "Default")
      (node (ref "C_CLKOUT1") (pin "TP") (pinfunction "TP_TP") (pintype "input"))
      (node (ref "U$2") (pin "43") (pinfunction "CORE_CLOCKOUT_43") (pintype "bidirectional"))
    )
    (net (code "46") (name "Net-(U$2-VDDA_PLL)") (class "Default")
      (node (ref "C14") (pin "2") (pinfunction "2_2") (pintype "passive"))
      (node (ref "R3") (pin "2") (pinfunction "2_2") (pintype "passive"))
      (node (ref "U$2") (pin "6") (pinfunction "VDDA_PLL_6") (pintype "bidirectional"))
      (node (ref "U$2") (pin "7") (pinfunction "VDD_PLL_7") (pintype "bidirectional"))
    )
    (net (code "47") (name "Net-(U$3-CORE_CLOCKOUT)") (class "Default")
      (node (ref "C_CLKOUT2") (pin "TP") (pinfunction "TP_TP") (pintype "input"))
      (node (ref "U$3") (pin "43") (pinfunction "CORE_CLOCKOUT_43") (pintype "bidirectional"))
    )
    (net (code "48") (name "Net-(U$3-VDDA_PLL)") (class "Default")
      (node (ref "C26") (pin "2") (pinfunction "2_2") (pintype "passive"))
      (node (ref "R5") (pin "2") (pinfunction "2_2") (pintype "passive"))
      (node (ref "U$3") (pin "6") (pinfunction "VDDA_PLL_6") (pintype "bidirectional"))
      (node (ref "U$3") (pin "7") (pinfunction "VDD_PLL_7") (pintype "bidirectional"))
    )
    (net (code "49") (name "Net-(U$4-CORE_CLOCKOUT)") (class "Default")
      (node (ref "C_CLKOUT3") (pin "TP") (pinfunction "TP_TP") (pintype "input"))
      (node (ref "U$4") (pin "43") (pinfunction "CORE_CLOCKOUT_43") (pintype "bidirectional"))
    )
    (net (code "50") (name "Net-(U$4-VDDA_PLL)") (class "Default")
      (node (ref "C38") (pin "2") (pinfunction "2_2") (pintype "passive"))
      (node (ref "R7") (pin "2") (pinfunction "2_2") (pintype "passive"))
      (node (ref "U$4") (pin "6") (pinfunction "VDDA_PLL_6") (pintype "bidirectional"))
      (node (ref "U$4") (pin "7") (pinfunction "VDD_PLL_7") (pintype "bidirectional"))
    )
    (net (code "51") (name "Net-(U$5-CORE_CLOCKOUT)") (class "Default")
      (node (ref "C_CLKOUT4") (pin "TP") (pinfunction "TP_TP") (pintype "input"))
      (node (ref "U$5") (pin "43") (pinfunction "CORE_CLOCKOUT_43") (pintype "bidirectional"))
    )
    (net (code "52") (name "Net-(U$5-VDDA_PLL)") (class "Default")
      (node (ref "C50") (pin "2") (pinfunction "2_2") (pintype "passive"))
      (node (ref "R9") (pin "2") (pinfunction "2_2") (pintype "passive"))
      (node (ref "U$5") (pin "6") (pinfunction "VDDA_PLL_6") (pintype "bidirectional"))
      (node (ref "U$5") (pin "7") (pinfunction "VDD_PLL_7") (pintype "bidirectional"))
    )
    (net (code "53") (name "Net-(U$6-CORE_CLOCKOUT)") (class "Default")
      (node (ref "C_CLKOUT5") (pin "TP") (pinfunction "TP_TP") (pintype "input"))
      (node (ref "U$6") (pin "43") (pinfunction "CORE_CLOCKOUT_43") (pintype "bidirectional"))
    )
    (net (code "54") (name "Net-(U$6-VDDA_PLL)") (class "Default")
      (node (ref "C62") (pin "2") (pinfunction "2_2") (pintype "passive"))
      (node (ref "R11") (pin "2") (pinfunction "2_2") (pintype "passive"))
      (node (ref "U$6") (pin "6") (pinfunction "VDDA_PLL_6") (pintype "bidirectional"))
      (node (ref "U$6") (pin "7") (pinfunction "VDD_PLL_7") (pintype "bidirectional"))
    )
    (net (code "55") (name "Net-(U$7-CORE_CLOCKOUT)") (class "Default")
      (node (ref "C_CLKOUT6") (pin "TP") (pinfunction "TP_TP") (pintype "input"))
      (node (ref "U$7") (pin "43") (pinfunction "CORE_CLOCKOUT_43") (pintype "bidirectional"))
    )
    (net (code "56") (name "Net-(U$7-VDDA_PLL)") (class "Default")
      (node (ref "C74") (pin "2") (pinfunction "2_2") (pintype "passive"))
      (node (ref "R13") (pin "2") (pinfunction "2_2") (pintype "passive"))
      (node (ref "U$7") (pin "6") (pinfunction "VDDA_PLL_6") (pintype "bidirectional"))
      (node (ref "U$7") (pin "7") (pinfunction "VDD_PLL_7") (pintype "bidirectional"))
    )
    (net (code "57") (name "Net-(U$8-CORE_CLOCKOUT)") (class "Default")
      (node (ref "C_CLKOUT7") (pin "TP") (pinfunction "TP_TP") (pintype "input"))
      (node (ref "U$8") (pin "43") (pinfunction "CORE_CLOCKOUT_43") (pintype "bidirectional"))
    )
    (net (code "58") (name "Net-(U$8-VDDA_PLL)") (class "Default")
      (node (ref "C86") (pin "2") (pinfunction "2_2") (pintype "passive"))
      (node (ref "R15") (pin "2") (pinfunction "2_2") (pintype "passive"))
      (node (ref "U$8") (pin "6") (pinfunction "VDDA_PLL_6") (pintype "bidirectional"))
      (node (ref "U$8") (pin "7") (pinfunction "VDD_PLL_7") (pintype "bidirectional"))
    )
    (net (code "59") (name "Net-(U$9-CORE_CLOCKOUT)") (class "Default")
      (node (ref "C_CLKOUT8") (pin "TP") (pinfunction "TP_TP") (pintype "input"))
      (node (ref "U$9") (pin "43") (pinfunction "CORE_CLOCKOUT_43") (pintype "bidirectional"))
    )
    (net (code "60") (name "Net-(U$9-VDDA_PLL)") (class "Default")
      (node (ref "C98") (pin "2") (pinfunction "2_2") (pintype "passive"))
      (node (ref "R17") (pin "2") (pinfunction "2_2") (pintype "passive"))
      (node (ref "U$9") (pin "6") (pinfunction "VDDA_PLL_6") (pintype "bidirectional"))
      (node (ref "U$9") (pin "7") (pinfunction "VDD_PLL_7") (pintype "bidirectional"))
    )
    (net (code "61") (name "Net-(U$10-CORE_CLOCKOUT)") (class "Default")
      (node (ref "C_CLKOUT9") (pin "TP") (pinfunction "TP_TP") (pintype "input"))
      (node (ref "U$10") (pin "43") (pinfunction "CORE_CLOCKOUT_43") (pintype "bidirectional"))
    )
    (net (code "62") (name "Net-(U$10-VDDA_PLL)") (class "Default")
      (node (ref "C110") (pin "2") (pinfunction "2_2") (pintype "passive"))
      (node (ref "R19") (pin "2") (pinfunction "2_2") (pintype "passive"))
      (node (ref "U$10") (pin "6") (pinfunction "VDDA_PLL_6") (pintype "bidirectional"))
      (node (ref "U$10") (pin "7") (pinfunction "VDD_PLL_7") (pintype "bidirectional"))
    )
    (net (code "63") (name "Net-(X1A-S)") (class "Default")
      (node (ref "THERMISTOR") (pin "1") (pinfunction "1_1") (pintype "passive"))
      (node (ref "X1") (pin "1") (pinfunction "S_1") (pintype "passive"))
    )
    (net (code "64") (name "Net-(X1B-S)") (class "Default")
      (node (ref "THERMISTOR") (pin "2") (pinfunction "2_2") (pintype "passive"))
      (node (ref "X1") (pin "2") (pinfunction "S_2") (pintype "passive"))
    )
  )
)
